# BEP33_2panel_test.net
KiCad netlist of a schematic drawn in EAGLE
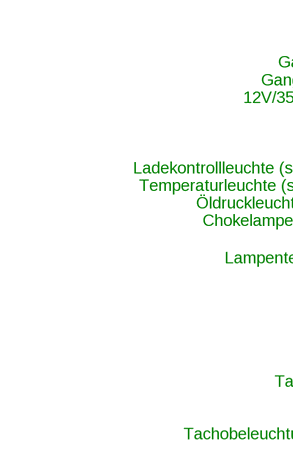
[diagram p0: schematic, sheet 1, part 1 of 2]
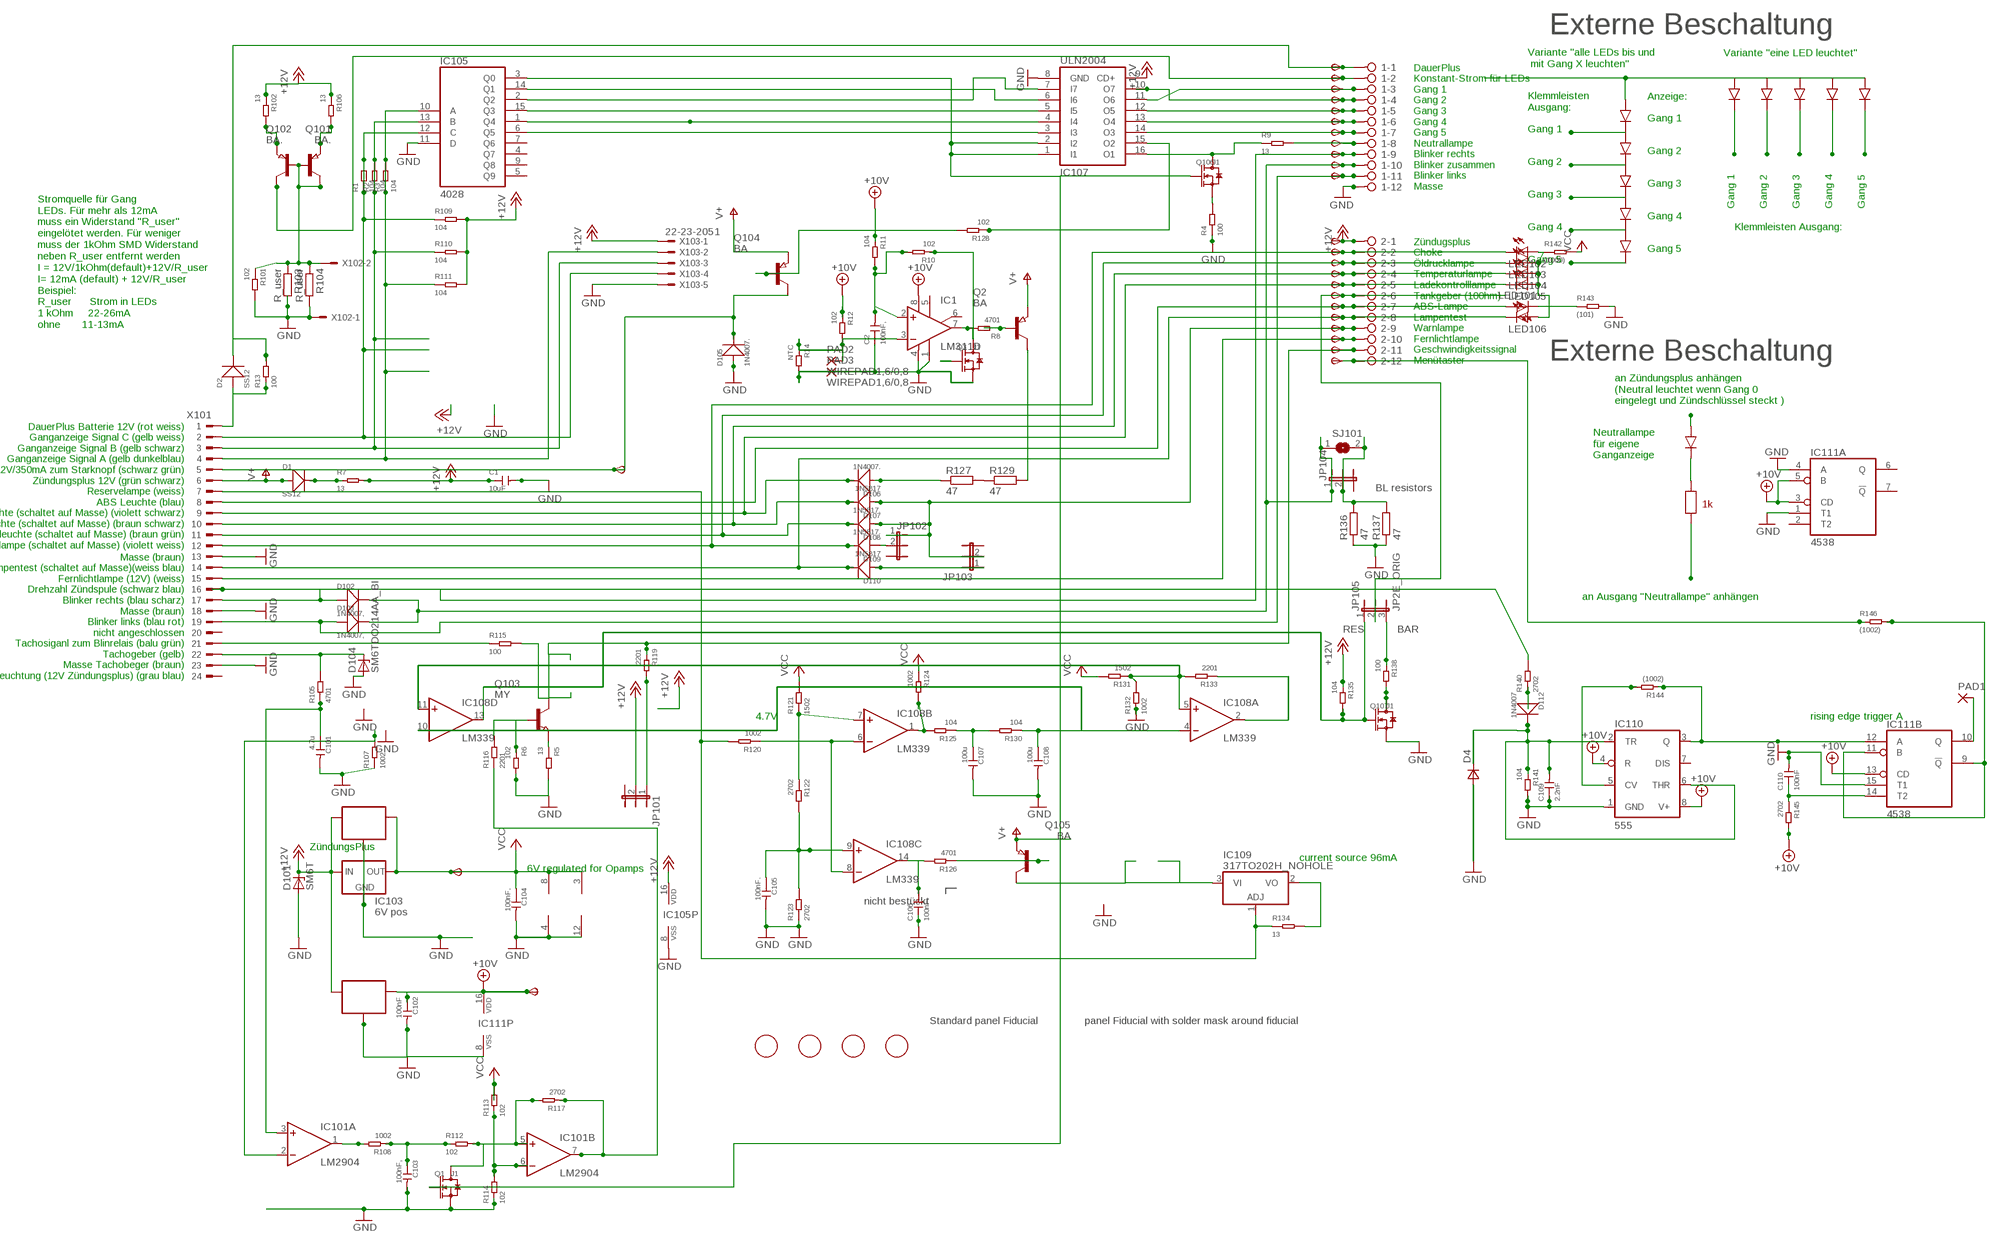
[diagram p1: schematic, sheet 1, part 2 of 2]
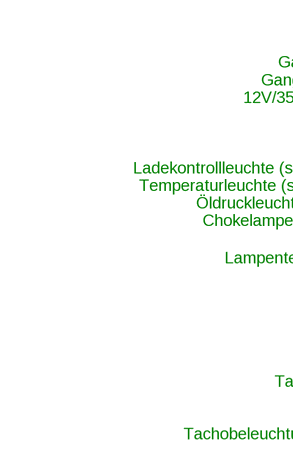
[diagram p2: schematic, sheet 2, part 1 of 2]
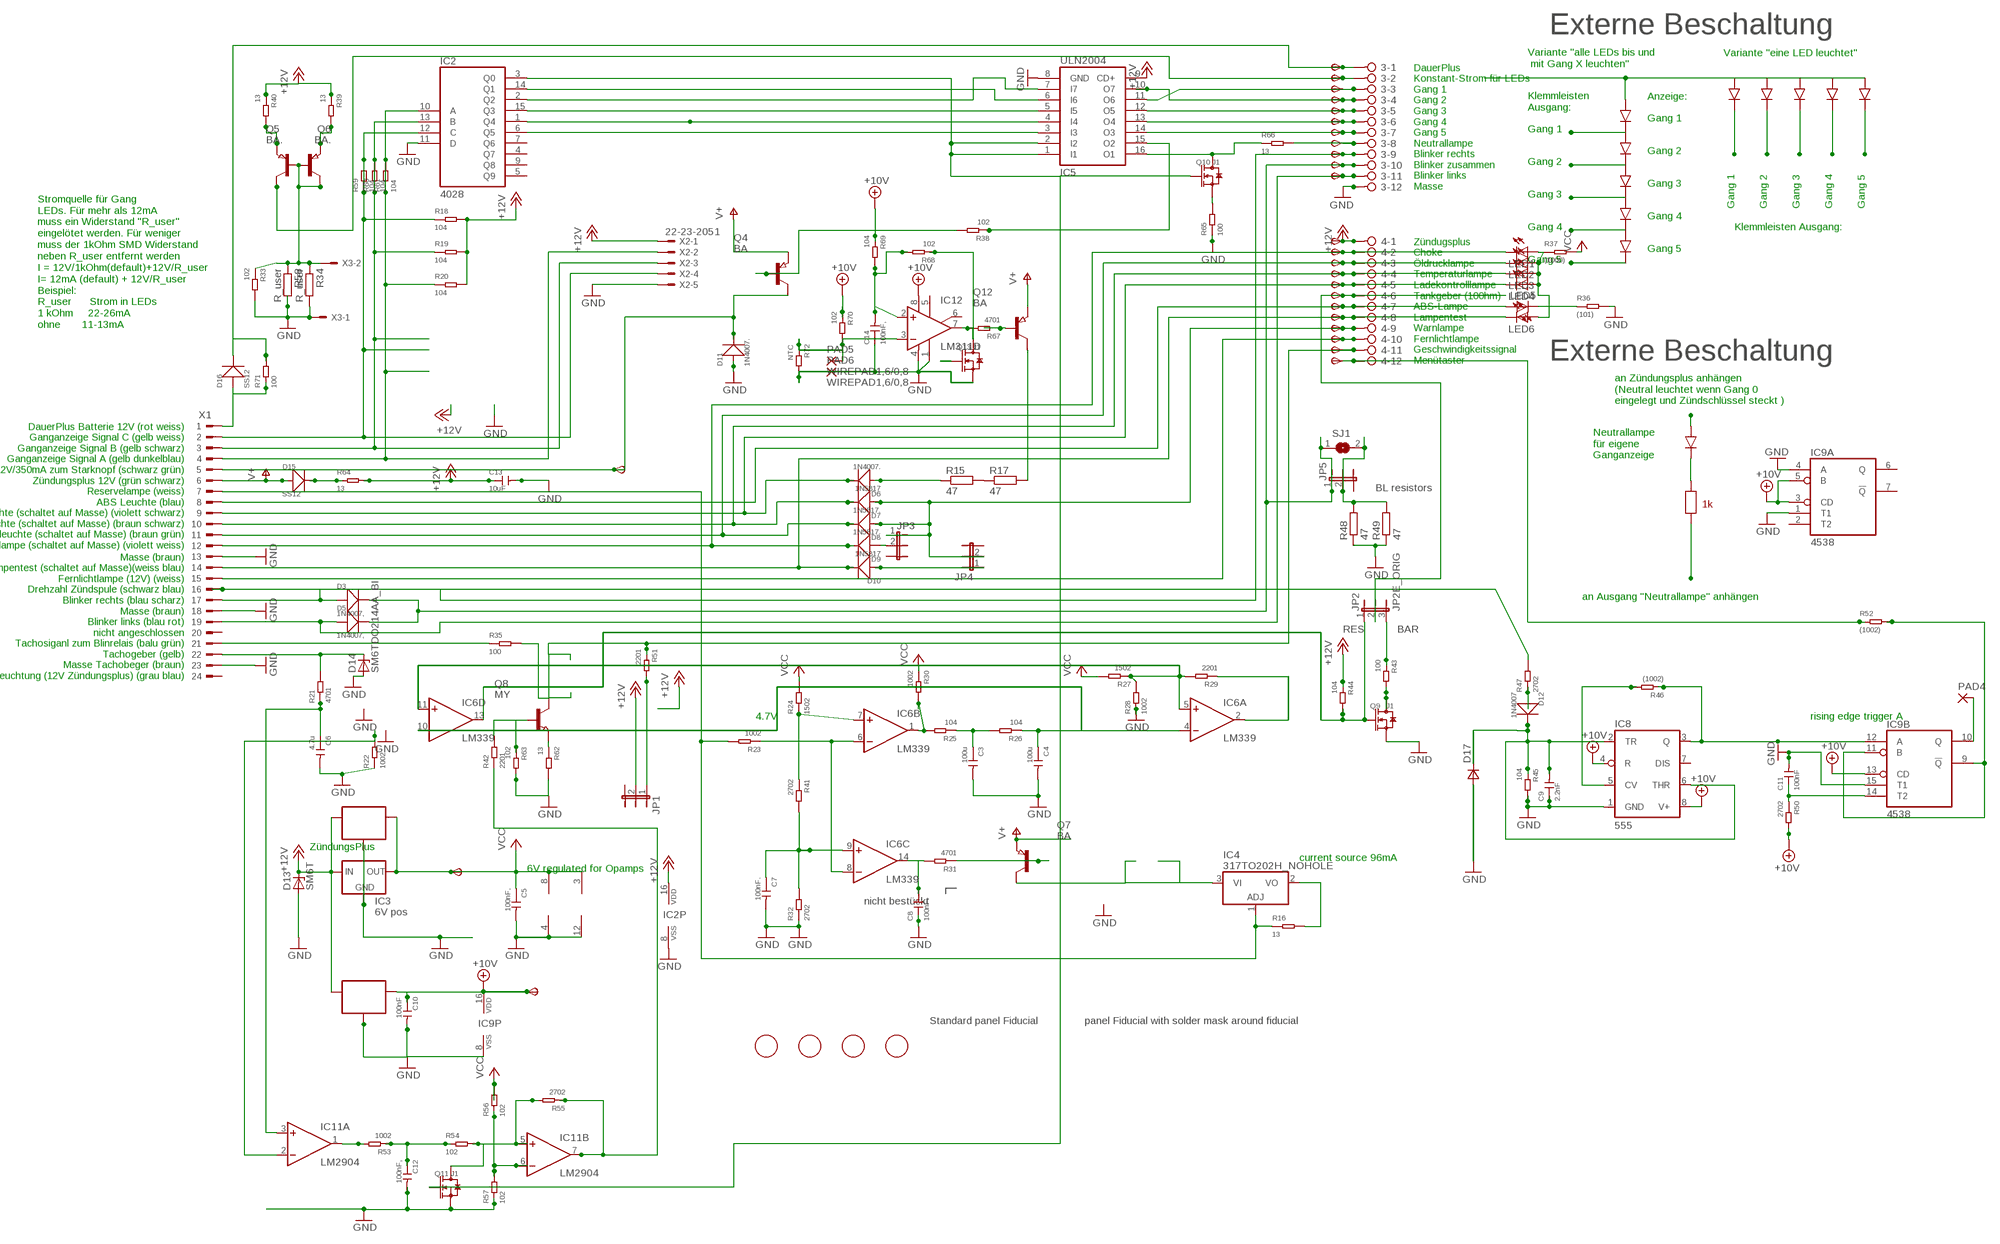
[diagram p3: schematic, sheet 2, part 2 of 2]

(export (version "E")
  (design (tool "Eeschema 10.0.6"))
  (components
    (comp (ref "3")
      (value "2081-1132")
      (footprint "eagle-import:12-PIN")
      (libsource (lib "eagle-import") (part "2081-1132"))
    )
    (comp (ref "4")
      (value "2081-1132")
      (footprint "eagle-import:12-PIN")
      (libsource (lib "eagle-import") (part "2081-1132"))
    )
    (comp (ref "6V1")
      (value "TPSB2.0")
      (footprint "eagle-import:B2.0")
      (libsource (lib "eagle-import") (part "TPSB2.0"))
    )
    (comp (ref "10V1")
      (value "TPSB2.0")
      (footprint "eagle-import:B2.0")
      (libsource (lib "eagle-import") (part "TPSB2.0"))
    )
    (comp (ref "C3")
      (value "100u")
      (footprint "eagle-import:C1206")
      (fields (field (name "MPN") "GRM31CR60J107ME39L"))
      (libsource (lib "eagle-import") (part "CERAMIC-100UF-6.3V-20%-X5R(1206)"))
    )
    (comp (ref "C4")
      (value "100u")
      (footprint "eagle-import:C1206")
      (fields (field (name "MPN") "GRM31CR60J107ME39L"))
      (libsource (lib "eagle-import") (part "CERAMIC-100UF-6.3V-20%-X5R(1206)"))
    )
    (comp (ref "C5")
      (value "100nF,")
      (footprint "eagle-import:C0805")
      (fields (field (name "MPN") "CC0805KRX7R9BB104"))
      (libsource (lib "eagle-import") (part "CERAMIC-100NF-50V-10%-X7R(0805)"))
    )
    (comp (ref "C6")
      (value "4.7u")
      (footprint "eagle-import:C0805")
      (fields (field (name "MPN") "CC0805KKX5R8BB475"))
      (libsource (lib "eagle-import") (part "CERAMIC-4.7UF-25V-10%-X5R(0805)"))
    )
    (comp (ref "C7")
      (value "100nF.")
      (footprint "eagle-import:C0805")
      (fields (field (name "MPN") "CC0805KRX7R9BB104"))
      (libsource (lib "eagle-import") (part "CERAMIC-100NF-50V-10%-X7R(0805)"))
    )
    (comp (ref "C8")
      (value "100nF.")
      (footprint "eagle-import:C0805")
      (fields (field (name "MPN") "CC0805KRX7R9BB104"))
      (libsource (lib "eagle-import") (part "CERAMIC-100NF-50V-10%-X7R(0805)"))
    )
    (comp (ref "C9")
      (value "2.2nF")
      (footprint "eagle-import:C0805")
      (fields (field (name "MPN") "CC0805KRX7R9BB104"))
      (libsource (lib "eagle-import") (part "CERAMIC-100NF-50V-10%-X7R(0805)"))
    )
    (comp (ref "C10")
      (value "100nF")
      (footprint "eagle-import:C0805")
      (fields (field (name "MPN") "CC0805KRX7R9BB104"))
      (libsource (lib "eagle-import") (part "CERAMIC-100NF-50V-10%-X7R(0805)"))
    )
    (comp (ref "C11")
      (value "100nF")
      (footprint "eagle-import:C0805")
      (fields (field (name "MPN") "CC0805KRX7R9BB104"))
      (libsource (lib "eagle-import") (part "CERAMIC-100NF-50V-10%-X7R(0805)"))
    )
    (comp (ref "C12")
      (value "100nF,")
      (footprint "eagle-import:C0805")
      (fields (field (name "MPN") "CC0805KRX7R9BB104"))
      (libsource (lib "eagle-import") (part "CERAMIC-100NF-50V-10%-X7R(0805)"))
    )
    (comp (ref "C13")
      (value "10uF")
      (footprint "eagle-import:C0805")
      (fields (field (name "MPN") "CC0805KRX7R9BB104"))
      (libsource (lib "eagle-import") (part "CERAMIC-100NF-50V-10%-X7R(0805)"))
    )
    (comp (ref "C14")
      (value "100nF,")
      (footprint "eagle-import:C0805")
      (fields (field (name "MPN") "CC0805KRX7R9BB104"))
      (libsource (lib "eagle-import") (part "CERAMIC-100NF-50V-10%-X7R(0805)"))
    )
    (comp (ref "D3")
      (value "1N4007,")
      (footprint "eagle-import:DO-214AC")
      (fields (field (name "MPN") "1N4007"))
      (libsource (lib "eagle-import") (part "DIODE-GEN-PURPOSE-1KV-1A(DO-214AC)"))
    )
    (comp (ref "D5")
      (value "1N4007,")
      (footprint "eagle-import:DO-214AC")
      (fields (field (name "MPN") "1N4007"))
      (libsource (lib "eagle-import") (part "DIODE-GEN-PURPOSE-1KV-1A(DO-214AC)"))
    )
    (comp (ref "D6")
      (value "1N4007.")
      (footprint "eagle-import:DO-214AC")
      (fields (field (name "MPN") "1N4007"))
      (libsource (lib "eagle-import") (part "DIODE-GEN-PURPOSE-1KV-1A(DO-214AC)"))
    )
    (comp (ref "D7")
      (value "1N5817")
      (footprint "eagle-import:DO-214AC_SLIM")
      (libsource (lib "eagle-import") (part "DIODE-GEN-PURPOSE-1KV-1A(DO-214AC)DO-214AC/1206"))
    )
    (comp (ref "D8")
      (value "1N5817.")
      (footprint "eagle-import:DO-214AC_SLIM")
      (libsource (lib "eagle-import") (part "DIODE-GEN-PURPOSE-1KV-1A(DO-214AC)DO-214AC/1206"))
    )
    (comp (ref "D9")
      (value "1N5817.")
      (footprint "eagle-import:DO-214AC_SLIM")
      (libsource (lib "eagle-import") (part "DIODE-GEN-PURPOSE-1KV-1A(DO-214AC)DO-214AC/1206"))
    )
    (comp (ref "D10")
      (value "1N5817")
      (footprint "eagle-import:DO-214AC_SLIM")
      (libsource (lib "eagle-import") (part "DIODE-GEN-PURPOSE-1KV-1A(DO-214AC)DO-214AC/1206"))
    )
    (comp (ref "D11")
      (value "1N4007.")
      (footprint "eagle-import:DO-214AC")
      (fields (field (name "MPN") "1N4007"))
      (libsource (lib "eagle-import") (part "DIODE-GEN-PURPOSE-1KV-1A(DO-214AC)"))
    )
    (comp (ref "D12")
      (value "1N4007")
      (footprint "eagle-import:DO-214AC")
      (libsource (lib "eagle-import") (part "DIODE-GEN-PURPOSE-1KV-1A(DO-214AC)"))
    )
    (comp (ref "D13")
      (value "SM6T")
      (footprint "eagle-import:DO214AA")
      (libsource (lib "eagle-import") (part "SM6T"))
    )
    (comp (ref "D14")
      (value "SM6TDO214AA_BI")
      (footprint "eagle-import:DO214AA_BI")
      (libsource (lib "eagle-import") (part "SM6TDO214AA_BI"))
    )
    (comp (ref "D15")
      (value "SS12")
      (footprint "eagle-import:DO-214AC_SLIM")
      (libsource (lib "eagle-import") (part "DIODE-GEN-PURPOSE-1KV-1A(DO-214AC)DO-214AC/1206"))
    )
    (comp (ref "D16")
      (value "SS12")
      (footprint "eagle-import:DO-214AC_SLIM")
      (libsource (lib "eagle-import") (part "DIODE-GEN-PURPOSE-1KV-1A(DO-214AC)DO-214AC/1206"))
    )
    (comp (ref "D17")
      (value "DSOD323")
      (footprint "eagle-import:SOD323")
      (fields (field (name "MPN") "CDSOD323-T05C"))
      (libsource (lib "eagle-import") (part "DSOD323"))
    )
    (comp (ref "FID3")
      (value "FIDUCIAL")
      (footprint "eagle-import:FIDUCIAL_1MM")
      (libsource (lib "eagle-import") (part "FIDUCIAL"))
    )
    (comp (ref "FID4")
      (value "FIDUCIAL")
      (footprint "eagle-import:FIDUCIAL_1MM")
      (libsource (lib "eagle-import") (part "FIDUCIAL"))
    )
    (comp (ref "FID5")
      (value "FIDUCIAL")
      (footprint "eagle-import:FIDUCIAL_1MM")
      (libsource (lib "eagle-import") (part "FIDUCIAL"))
    )
    (comp (ref "FID6")
      (value "FIDUCIAL")
      (footprint "eagle-import:FIDUCIAL_1MM")
      (libsource (lib "eagle-import") (part "FIDUCIAL"))
    )
    (comp (ref "IC2")
      (value "4028")
      (footprint "eagle-import:SO16")
      (libsource (lib "eagle-import") (part "4028D"))
    )
    (comp (ref "IC3")
      (value "6V pos")
      (footprint "eagle-import:78LXX")
      (libsource (lib "eagle-import") (part "v-reg_78LXX"))
    )
    (comp (ref "IC4")
      (value "317TO202H_NOHOLE")
      (footprint "eagle-import:TO220H_NOHOLE")
      (libsource (lib "eagle-import") (part "317TO202H_NOHOLE"))
    )
    (comp (ref "IC5")
      (value "ULN2004")
      (footprint "eagle-import:SO16")
      (libsource (lib "eagle-import") (part "ULN2004AD"))
    )
    (comp (ref "IC6")
      (value "LM339")
      (footprint "eagle-import:SO14")
      (libsource (lib "eagle-import") (part "LM339D"))
    )
    (comp (ref "IC7")
      (value "78L06")
      (footprint "eagle-import:SOT89_ROUND")
      (libsource (lib "eagle-import") (part "78LXXSOT89_ROUND"))
    )
    (comp (ref "IC8")
      (value "555")
      (footprint "eagle-import:SO08")
      (libsource (lib "eagle-import") (part "555DNE"))
    )
    (comp (ref "IC9")
      (value "4538")
      (footprint "eagle-import:SO16")
      (libsource (lib "eagle-import") (part "4538D"))
    )
    (comp (ref "IC10")
      (value "78L10")
      (footprint "eagle-import:SOT89_ROUND")
      (libsource (lib "eagle-import") (part "78LXXSOT89_ROUND"))
    )
    (comp (ref "IC11")
      (value "LM2904")
      (footprint "eagle-import:SO08")
      (libsource (lib "eagle-import") (part "LM358D"))
    )
    (comp (ref "IC12")
      (value "LM311D")
      (footprint "eagle-import:SO08")
      (libsource (lib "eagle-import") (part "LM311D"))
    )
    (comp (ref "JP1")
      (value "JP2EJP2_SMALLPADS")
      (footprint "eagle-import:JP2_SMALLPADS")
      (libsource (lib "eagle-import") (part "JP2EJP2_SMALLPADS"))
    )
    (comp (ref "JP2")
      (value "JP2E_ORIG")
      (footprint "eagle-import:JP2_ORIG_SMALLPADS")
      (libsource (lib "eagle-import") (part "JP2E_ORIG"))
    )
    (comp (ref "JP3")
      (value "JP2EJP2_SMALLPADS")
      (footprint "eagle-import:JP2_SMALLPADS")
      (libsource (lib "eagle-import") (part "JP2EJP2_SMALLPADS"))
    )
    (comp (ref "JP4")
      (value "JP2EJP2_SMALLPADS")
      (footprint "eagle-import:JP2_SMALLPADS")
      (libsource (lib "eagle-import") (part "JP2EJP2_SMALLPADS"))
    )
    (comp (ref "JP5")
      (value "JP2EJP2_SMALLPADS")
      (footprint "eagle-import:JP2_SMALLPADS")
      (libsource (lib "eagle-import") (part "JP2EJP2_SMALLPADS"))
    )
    (comp (ref "LED1")
      (value "LEDLD260")
      (footprint "eagle-import:LD260")
      (libsource (lib "eagle-import") (part "LEDLD260"))
    )
    (comp (ref "LED2")
      (value "LEDLD260")
      (footprint "eagle-import:LD260")
      (libsource (lib "eagle-import") (part "LEDLD260"))
    )
    (comp (ref "LED3")
      (value "LEDLD260")
      (footprint "eagle-import:LD260")
      (libsource (lib "eagle-import") (part "LEDLD260"))
    )
    (comp (ref "LED4")
      (value "LEDLD260")
      (footprint "eagle-import:LD260")
      (libsource (lib "eagle-import") (part "LEDLD260"))
    )
    (comp (ref "LED5")
      (value "LEDLD260")
      (footprint "eagle-import:LD260")
      (libsource (lib "eagle-import") (part "LEDLD260"))
    )
    (comp (ref "LED6")
      (value "LEDLD260")
      (footprint "eagle-import:LD260")
      (libsource (lib "eagle-import") (part "LEDLD260"))
    )
    (comp (ref "PAD4")
      (value "1,6/0,8")
      (footprint "eagle-import:1,6_0,8")
      (libsource (lib "eagle-import") (part "1,6/0,8"))
    )
    (comp (ref "PAD5")
      (value "WIREPAD1,6/0,8")
      (footprint "eagle-import:1,6_0,8")
      (libsource (lib "eagle-import") (part "WIREPAD1,6/0,8"))
    )
    (comp (ref "PAD6")
      (value "WIREPAD1,6/0,8")
      (footprint "eagle-import:1,6_0,8")
      (libsource (lib "eagle-import") (part "WIREPAD1,6/0,8"))
    )
    (comp (ref "Q4")
      (value "BA")
      (footprint "eagle-import:SOT89")
      (libsource (lib "eagle-import") (part "PNP-TRANSISTOR_SOT89"))
    )
    (comp (ref "Q5")
      (value "BA.")
      (footprint "eagle-import:SOT89")
      (libsource (lib "eagle-import") (part "PNP-TRANSISTOR_SOT89"))
    )
    (comp (ref "Q6")
      (value "BA.")
      (footprint "eagle-import:SOT89")
      (libsource (lib "eagle-import") (part "PNP-TRANSISTOR_SOT89"))
    )
    (comp (ref "Q7")
      (value "BA")
      (footprint "eagle-import:SOT89")
      (libsource (lib "eagle-import") (part "PNP-TRANSISTOR_SOT89"))
    )
    (comp (ref "Q8")
      (value "MY")
      (footprint "eagle-import:SOT89")
      (libsource (lib "eagle-import") (part "NPN-TRANSISTOR_SOT89"))
    )
    (comp (ref "Q9")
      (value "J1")
      (footprint "eagle-import:SOT-23")
      (fields (field (name "MPN") "BSS138W-7-F"))
      (libsource (lib "eagle-import") (part "SMD-MOSFET-N-CH-50V-200MA-BSS138W-7-F(SOT-23)"))
    )
    (comp (ref "Q10")
      (value "J1")
      (footprint "eagle-import:SOT-23")
      (fields (field (name "MPN") "BSS138W-7-F"))
      (libsource (lib "eagle-import") (part "SMD-MOSFET-N-CH-50V-200MA-BSS138W-7-F(SOT-23)"))
    )
    (comp (ref "Q11")
      (value "J1")
      (footprint "eagle-import:SOT-23")
      (fields (field (name "MPN") "BSS138W-7-F"))
      (libsource (lib "eagle-import") (part "SMD-MOSFET-N-CH-50V-200MA-BSS138W-7-F(SOT-23)"))
    )
    (comp (ref "Q12")
      (value "BA")
      (footprint "eagle-import:SOT89")
      (libsource (lib "eagle-import") (part "PNP-TRANSISTOR_SOT89"))
    )
    (comp (ref "Q13")
      (value "J1")
      (footprint "eagle-import:SOT-23")
      (fields (field (name "MPN") "BSS138W-7-F"))
      (libsource (lib "eagle-import") (part "SMD-MOSFET-N-CH-50V-200MA-BSS138W-7-F(SOT-23)"))
    )
    (comp (ref "R15")
      (value "47")
      (footprint "eagle-import:V235_17_1MM")
      (libsource (lib "eagle-import") (part "R-EU_V235/17_1MM"))
    )
    (comp (ref "R16")
      (value "13")
      (footprint "eagle-import:R1206")
      (fields (field (name "MPN") "RC1206JR-0713RL"))
      (libsource (lib "eagle-import") (part "SMD-RES-13R-5%-1/4W(1206)"))
    )
    (comp (ref "R17")
      (value "47")
      (footprint "eagle-import:V235_17_1MM")
      (libsource (lib "eagle-import") (part "R-EU_V235/17_1MM"))
    )
    (comp (ref "R18")
      (value "104")
      (footprint "eagle-import:R0805")
      (fields (field (name "MPN") "RC0805FR-0710KL"))
      (libsource (lib "eagle-import") (part "SMD-RES-10K-1%-1/8W(0805)"))
    )
    (comp (ref "R19")
      (value "104")
      (footprint "eagle-import:R0805")
      (fields (field (name "MPN") "RC0805FR-0710KL"))
      (libsource (lib "eagle-import") (part "SMD-RES-10K-1%-1/8W(0805)"))
    )
    (comp (ref "R20")
      (value "104")
      (footprint "eagle-import:R0805")
      (fields (field (name "MPN") "RC0805FR-0710KL"))
      (libsource (lib "eagle-import") (part "SMD-RES-10K-1%-1/8W(0805)"))
    )
    (comp (ref "R21")
      (value "4701")
      (footprint "eagle-import:R0805")
      (fields (field (name "MPN") "RC0805JR-074K7L"))
      (libsource (lib "eagle-import") (part "SMD-RES-4.7K-5%-1/8W(0805)"))
    )
    (comp (ref "R22")
      (value "1002")
      (footprint "eagle-import:R0805")
      (fields (field (name "MPN") "RC0805FR-0710KL"))
      (libsource (lib "eagle-import") (part "SMD-RES-10K-1%-1/8W(0805)"))
    )
    (comp (ref "R23")
      (value "1002")
      (footprint "eagle-import:R0805")
      (fields (field (name "MPN") "RC0805FR-0710KL"))
      (libsource (lib "eagle-import") (part "SMD-RES-10K-1%-1/8W(0805)"))
    )
    (comp (ref "R24")
      (value "1502")
      (footprint "eagle-import:R0805")
      (fields (field (name "MPN") "RC0805FR-0710KL"))
      (libsource (lib "eagle-import") (part "SMD-RES-10K-1%-1/8W(0805)"))
    )
    (comp (ref "R25")
      (value "104")
      (footprint "eagle-import:R0805")
      (fields (field (name "MPN") "RC0805FR-0710KL"))
      (libsource (lib "eagle-import") (part "SMD-RES-10K-1%-1/8W(0805)"))
    )
    (comp (ref "R26")
      (value "104")
      (footprint "eagle-import:R0805")
      (fields (field (name "MPN") "RC0805FR-0710KL"))
      (libsource (lib "eagle-import") (part "SMD-RES-10K-1%-1/8W(0805)"))
    )
    (comp (ref "R27")
      (value "1502")
      (footprint "eagle-import:R0805")
      (fields (field (name "MPN") "RC0805FR-0710KL"))
      (libsource (lib "eagle-import") (part "SMD-RES-10K-1%-1/8W(0805)"))
    )
    (comp (ref "R28")
      (value "1002")
      (footprint "eagle-import:R0805")
      (fields (field (name "MPN") "RC0805FR-0710KL"))
      (libsource (lib "eagle-import") (part "SMD-RES-10K-1%-1/8W(0805)"))
    )
    (comp (ref "R29")
      (value "2201")
      (footprint "eagle-import:R0805")
      (fields (field (name "MPN") "RC0805JR-072K2L"))
      (libsource (lib "eagle-import") (part "SMD-RES-2.2K-5%-1/8W(0805)"))
    )
    (comp (ref "R30")
      (value "1002")
      (footprint "eagle-import:R0805")
      (fields (field (name "MPN") "RC0805FR-0710KL"))
      (libsource (lib "eagle-import") (part "SMD-RES-10K-1%-1/8W(0805)"))
    )
    (comp (ref "R31")
      (value "4701")
      (footprint "eagle-import:R0805")
      (fields (field (name "MPN") "RC0805JR-074K7L"))
      (libsource (lib "eagle-import") (part "SMD-RES-4.7K-5%-1/8W(0805)"))
    )
    (comp (ref "R32")
      (value "2702")
      (footprint "eagle-import:R0805")
      (fields (field (name "MPN") "RC0805JR-074K7L"))
      (libsource (lib "eagle-import") (part "SMD-RES-4.7K-5%-1/8W(0805)"))
    )
    (comp (ref "R33")
      (value "102")
      (footprint "eagle-import:R0805")
      (fields (field (name "MPN") "RC0805JR-071KL"))
      (libsource (lib "eagle-import") (part "SMD-RES-1K-5%-1/8W(0805)"))
    )
    (comp (ref "R34")
      (value "R_user")
      (footprint "eagle-import:R0805")
      (libsource (lib "eagle-import") (part "R-EU_R0805"))
    )
    (comp (ref "R35")
      (value "100")
      (footprint "eagle-import:R0805")
      (fields (field (name "MPN") "RC0805JR-07220RL"))
      (libsource (lib "eagle-import") (part "SMD-RES-220R-5%-1/8W(0805)"))
    )
    (comp (ref "R36")
      (value "(101)")
      (footprint "eagle-import:R0805")
      (fields (field (name "MPN") "RC0805JR-07100RL"))
      (libsource (lib "eagle-import") (part "SMD-RES-100R-5%-1/8W(0805)"))
    )
    (comp (ref "R37")
      (value "(1000)")
      (footprint "eagle-import:R0805")
      (fields (field (name "MPN") "RC0805JR-07100RL"))
      (libsource (lib "eagle-import") (part "SMD-RES-100R-5%-1/8W(0805)"))
    )
    (comp (ref "R38")
      (value "102")
      (footprint "eagle-import:R0805")
      (fields (field (name "MPN") "RC0805JR-071KL"))
      (libsource (lib "eagle-import") (part "SMD-RES-1K-5%-1/8W(0805)"))
    )
    (comp (ref "R39")
      (value "13")
      (footprint "eagle-import:R1206")
      (fields (field (name "MPN") "RC1206JR-0713RL"))
      (libsource (lib "eagle-import") (part "SMD-RES-13R-5%-1/4W(1206)"))
    )
    (comp (ref "R40")
      (value "13")
      (footprint "eagle-import:R1206")
      (fields (field (name "MPN") "RC1206JR-0713RL"))
      (libsource (lib "eagle-import") (part "SMD-RES-13R-5%-1/4W(1206)"))
    )
    (comp (ref "R41")
      (value "2702")
      (footprint "eagle-import:R0805")
      (fields (field (name "MPN") "RC0805JR-074K7L"))
      (libsource (lib "eagle-import") (part "SMD-RES-4.7K-5%-1/8W(0805)"))
    )
    (comp (ref "R42")
      (value "2201")
      (footprint "eagle-import:R0805")
      (fields (field (name "MPN") "RC0805JR-074K7L"))
      (libsource (lib "eagle-import") (part "SMD-RES-4.7K-5%-1/8W(0805)"))
    )
    (comp (ref "R43")
      (value "100")
      (footprint "eagle-import:R0805")
      (fields (field (name "MPN") "RC0805JR-072K2L"))
      (libsource (lib "eagle-import") (part "SMD-RES-2.2K-5%-1/8W(0805)"))
    )
    (comp (ref "R44")
      (value "104")
      (footprint "eagle-import:R0805")
      (fields (field (name "MPN") "RC0805FR-0710KL"))
      (libsource (lib "eagle-import") (part "SMD-RES-10K-1%-1/8W(0805)"))
    )
    (comp (ref "R45")
      (value "104")
      (footprint "eagle-import:R0805")
      (fields (field (name "MPN") "RC0805FR-0710KL"))
      (libsource (lib "eagle-import") (part "SMD-RES-10K-1%-1/8W(0805)"))
    )
    (comp (ref "R46")
      (value "(1002)")
      (footprint "eagle-import:R0805")
      (fields (field (name "MPN") "RC0805FR-0710KL"))
      (libsource (lib "eagle-import") (part "SMD-RES-10K-1%-1/8W(0805)"))
    )
    (comp (ref "R47")
      (value "2702")
      (footprint "eagle-import:R0805")
      (fields (field (name "MPN") "RC0805FR-0710KL"))
      (libsource (lib "eagle-import") (part "SMD-RES-10K-1%-1/8W(0805)"))
    )
    (comp (ref "R48")
      (value "47")
      (footprint "eagle-import:V235_17_1MM")
      (libsource (lib "eagle-import") (part "R-EU_V235/17_1MM"))
    )
    (comp (ref "R49")
      (value "47")
      (footprint "eagle-import:V235_17_1MM")
      (libsource (lib "eagle-import") (part "R-EU_V235/17_1MM"))
    )
    (comp (ref "R50")
      (value "2702")
      (footprint "eagle-import:R0805")
      (fields (field (name "MPN") "RC0805JR-074K7L"))
      (libsource (lib "eagle-import") (part "SMD-RES-4.7K-5%-1/8W(0805)"))
    )
    (comp (ref "R51")
      (value "2201")
      (footprint "eagle-import:R0805")
      (fields (field (name "MPN") "RC0805JR-072K2L"))
      (libsource (lib "eagle-import") (part "SMD-RES-2.2K-5%-1/8W(0805)"))
    )
    (comp (ref "R52")
      (value "(1002)")
      (footprint "eagle-import:R0805")
      (fields (field (name "MPN") "RC0805JR-074K7L"))
      (libsource (lib "eagle-import") (part "SMD-RES-4.7K-5%-1/8W(0805)"))
    )
    (comp (ref "R53")
      (value "1002")
      (footprint "eagle-import:R0805")
      (fields (field (name "MPN") "RC0805FR-0710KL"))
      (libsource (lib "eagle-import") (part "SMD-RES-10K-1%-1/8W(0805)"))
    )
    (comp (ref "R54")
      (value "102")
      (footprint "eagle-import:R0805")
      (fields (field (name "MPN") "RC0805JR-071KL"))
      (libsource (lib "eagle-import") (part "SMD-RES-1K-5%-1/8W(0805)"))
    )
    (comp (ref "R55")
      (value "2702")
      (footprint "eagle-import:R0805")
      (fields (field (name "MPN") "RC0805JR-074K7L"))
      (libsource (lib "eagle-import") (part "SMD-RES-4.7K-5%-1/8W(0805)"))
    )
    (comp (ref "R56")
      (value "102")
      (footprint "eagle-import:R0805")
      (fields (field (name "MPN") "RC0805JR-071KL"))
      (libsource (lib "eagle-import") (part "SMD-RES-1K-5%-1/8W(0805)"))
    )
    (comp (ref "R57")
      (value "102")
      (footprint "eagle-import:R0805")
      (fields (field (name "MPN") "RC0805JR-071KL"))
      (libsource (lib "eagle-import") (part "SMD-RES-1K-5%-1/8W(0805)"))
    )
    (comp (ref "R58")
      (value "R_user")
      (footprint "eagle-import:R0805")
      (libsource (lib "eagle-import") (part "R-EU_R0805"))
    )
    (comp (ref "R59")
      (value "104")
      (footprint "eagle-import:R0805")
      (fields (field (name "MPN") "RC0805FR-0710KL"))
      (libsource (lib "eagle-import") (part "SMD-RES-10K-1%-1/8W(0805)"))
    )
    (comp (ref "R60")
      (value "104")
      (footprint "eagle-import:R0805")
      (fields (field (name "MPN") "RC0805FR-0710KL"))
      (libsource (lib "eagle-import") (part "SMD-RES-10K-1%-1/8W(0805)"))
    )
    (comp (ref "R61")
      (value "104")
      (footprint "eagle-import:R0805")
      (fields (field (name "MPN") "RC0805FR-0710KL"))
      (libsource (lib "eagle-import") (part "SMD-RES-10K-1%-1/8W(0805)"))
    )
    (comp (ref "R62")
      (value "13")
      (footprint "eagle-import:R1206")
      (fields (field (name "MPN") "RC1206JR-0713RL"))
      (libsource (lib "eagle-import") (part "SMD-RES-13R-5%-1/4W(1206)"))
    )
    (comp (ref "R63")
      (value "102")
      (footprint "eagle-import:R0805")
      (fields (field (name "MPN") "RC0805JR-071KL"))
      (libsource (lib "eagle-import") (part "SMD-RES-1K-5%-1/8W(0805)"))
    )
    (comp (ref "R64")
      (value "13")
      (footprint "eagle-import:R1206")
      (fields (field (name "MPN") "RC1206JR-0713RL"))
      (libsource (lib "eagle-import") (part "SMD-RES-13R-5%-1/4W(1206)"))
    )
    (comp (ref "R65")
      (value "100")
      (footprint "eagle-import:R0805")
      (fields (field (name "MPN") "RC0805JR-07220RL"))
      (libsource (lib "eagle-import") (part "SMD-RES-220R-5%-1/8W(0805)"))
    )
    (comp (ref "R66")
      (value "13")
      (footprint "eagle-import:R1206")
      (fields (field (name "MPN") "RC1206JR-0713RL"))
      (libsource (lib "eagle-import") (part "SMD-RES-13R-5%-1/4W(1206)"))
    )
    (comp (ref "R67")
      (value "4701")
      (footprint "eagle-import:R0805")
      (fields (field (name "MPN") "RC0805JR-074K7L"))
      (libsource (lib "eagle-import") (part "SMD-RES-4.7K-5%-1/8W(0805)"))
    )
    (comp (ref "R68")
      (value "102")
      (footprint "eagle-import:R0805")
      (fields (field (name "MPN") "RC0805JR-071KL"))
      (libsource (lib "eagle-import") (part "SMD-RES-1K-5%-1/8W(0805)"))
    )
    (comp (ref "R69")
      (value "104")
      (footprint "eagle-import:R0805")
      (fields (field (name "MPN") "RC0805FR-0710KL"))
      (libsource (lib "eagle-import") (part "SMD-RES-10K-1%-1/8W(0805)"))
    )
    (comp (ref "R70")
      (value "102")
      (footprint "eagle-import:R0805")
      (fields (field (name "MPN") "RC0805JR-071KL"))
      (libsource (lib "eagle-import") (part "SMD-RES-1K-5%-1/8W(0805)"))
    )
    (comp (ref "R71")
      (value "100")
      (footprint "eagle-import:R0805")
      (fields (field (name "MPN") "RC0805JR-07220RL"))
      (libsource (lib "eagle-import") (part "SMD-RES-220R-5%-1/8W(0805)"))
    )
    (comp (ref "R72")
      (value "NTC")
      (footprint "eagle-import:R0805")
      (fields (field (name "MPN") "RC0805JR-071KL"))
      (libsource (lib "eagle-import") (part "SMD-RES-1K-5%-1/8W(0805)"))
    )
    (comp (ref "SJ1") (value "SJ") (footprint "eagle-import:SJ") (libsource (lib "eagle-import") (part "SJ")))
    (comp (ref "START1")
      (value "TPSB2.0")
      (footprint "eagle-import:B2.0")
      (libsource (lib "eagle-import") (part "TPSB2.0"))
    )
    (comp (ref "TP14")
      (value "TPSB2.0")
      (footprint "eagle-import:B2.0")
      (libsource (lib "eagle-import") (part "TPSB2.0"))
    )
    (comp (ref "TP15")
      (value "TPSB2.0")
      (footprint "eagle-import:B2.0")
      (libsource (lib "eagle-import") (part "TPSB2.0"))
    )
    (comp (ref "TP20")
      (value "TPSB2.0")
      (footprint "eagle-import:B2.0")
      (libsource (lib "eagle-import") (part "TPSB2.0"))
    )
    (comp (ref "TP27")
      (value "TPSB2.0")
      (footprint "eagle-import:B2.0")
      (libsource (lib "eagle-import") (part "TPSB2.0"))
    )
    (comp (ref "TP28")
      (value "TPSB2.0")
      (footprint "eagle-import:B2.0")
      (libsource (lib "eagle-import") (part "TPSB2.0"))
    )
    (comp (ref "TP29")
      (value "TPSB2.0")
      (footprint "eagle-import:B2.0")
      (libsource (lib "eagle-import") (part "TPSB2.0"))
    )
    (comp (ref "TP30")
      (value "TPSB2.0")
      (footprint "eagle-import:B2.0")
      (libsource (lib "eagle-import") (part "TPSB2.0"))
    )
    (comp (ref "TP31")
      (value "TPSB2.0")
      (footprint "eagle-import:B2.0")
      (libsource (lib "eagle-import") (part "TPSB2.0"))
    )
    (comp (ref "TP32")
      (value "TPSB2.0")
      (footprint "eagle-import:B2.0")
      (libsource (lib "eagle-import") (part "TPSB2.0"))
    )
    (comp (ref "TP33")
      (value "TPSB2.0")
      (footprint "eagle-import:B2.0")
      (libsource (lib "eagle-import") (part "TPSB2.0"))
    )
    (comp (ref "TP34")
      (value "TPSB2.0")
      (footprint "eagle-import:B2.0")
      (libsource (lib "eagle-import") (part "TPSB2.0"))
    )
    (comp (ref "TP35")
      (value "TPSB2.0")
      (footprint "eagle-import:B2.0")
      (libsource (lib "eagle-import") (part "TPSB2.0"))
    )
    (comp (ref "TP36")
      (value "TPSB2.0")
      (footprint "eagle-import:B2.0")
      (libsource (lib "eagle-import") (part "TPSB2.0"))
    )
    (comp (ref "TP37")
      (value "TPSB2.0")
      (footprint "eagle-import:B2.0")
      (libsource (lib "eagle-import") (part "TPSB2.0"))
    )
    (comp (ref "TP38")
      (value "TPSB2.0")
      (footprint "eagle-import:B2.0")
      (libsource (lib "eagle-import") (part "TPSB2.0"))
    )
    (comp (ref "TP39")
      (value "TPSB2.0")
      (footprint "eagle-import:B2.0")
      (libsource (lib "eagle-import") (part "TPSB2.0"))
    )
    (comp (ref "TP40")
      (value "TPSB2.0")
      (footprint "eagle-import:B2.0")
      (libsource (lib "eagle-import") (part "TPSB2.0"))
    )
    (comp (ref "TP41")
      (value "TPSB2.0")
      (footprint "eagle-import:B2.0")
      (libsource (lib "eagle-import") (part "TPSB2.0"))
    )
    (comp (ref "TP42")
      (value "TPSB1,27")
      (footprint "eagle-import:B1,27")
      (libsource (lib "eagle-import") (part "TPSB1,27"))
    )
    (comp (ref "TP43")
      (value "TPSB2.0")
      (footprint "eagle-import:B2.0")
      (libsource (lib "eagle-import") (part "TPSB2.0"))
    )
    (comp (ref "TP44")
      (value "TPSB2.0")
      (footprint "eagle-import:B2.0")
      (libsource (lib "eagle-import") (part "TPSB2.0"))
    )
    (comp (ref "TP45")
      (value "TPSB2.0")
      (footprint "eagle-import:B2.0")
      (libsource (lib "eagle-import") (part "TPSB2.0"))
    )
    (comp (ref "TP46")
      (value "TPSB2.0")
      (footprint "eagle-import:B2.0")
      (libsource (lib "eagle-import") (part "TPSB2.0"))
    )
    (comp (ref "X1")
      (value "CON_BMWV2")
      (footprint "eagle-import:24-PIN_V2")
      (libsource (lib "eagle-import") (part "CON_BMWV2"))
    )
    (comp (ref "X2")
      (value "22-23-2051")
      (footprint "eagle-import:22-23-2051")
      (fields (field (name "MF") "MOLEX"))
      (libsource (lib "eagle-import") (part "22-23-2051"))
    )
    (comp (ref "X3")
      (value "22-23-2021")
      (footprint "eagle-import:22-23-2021")
      (fields (field (name "MF") "MOLEX"))
      (libsource (lib "eagle-import") (part "22-23-2021"))
    )
    (comp (ref "1")
      (value "2081-1132")
      (footprint "eagle-import:12-PIN")
      (libsource (lib "eagle-import") (part "2081-1132"))
    )
    (comp (ref "2")
      (value "2081-1132")
      (footprint "eagle-import:12-PIN")
      (libsource (lib "eagle-import") (part "2081-1132"))
    )
    (comp (ref "6V")
      (value "TPSB2.0")
      (footprint "eagle-import:B2.0")
      (libsource (lib "eagle-import") (part "TPSB2.0"))
    )
    (comp (ref "10V")
      (value "TPSB2.0")
      (footprint "eagle-import:B2.0")
      (libsource (lib "eagle-import") (part "TPSB2.0"))
    )
    (comp (ref "C1")
      (value "10uF")
      (footprint "eagle-import:C0805")
      (fields (field (name "MPN") "CC0805KRX7R9BB104"))
      (libsource (lib "eagle-import") (part "CERAMIC-100NF-50V-10%-X7R(0805)"))
    )
    (comp (ref "C2")
      (value "100nF,")
      (footprint "eagle-import:C0805")
      (fields (field (name "MPN") "CC0805KRX7R9BB104"))
      (libsource (lib "eagle-import") (part "CERAMIC-100NF-50V-10%-X7R(0805)"))
    )
    (comp (ref "C101")
      (value "4.7u")
      (footprint "eagle-import:C0805")
      (fields (field (name "MPN") "CC0805KKX5R8BB475"))
      (libsource (lib "eagle-import") (part "CERAMIC-4.7UF-25V-10%-X5R(0805)"))
    )
    (comp (ref "C102")
      (value "100nF")
      (footprint "eagle-import:C0805")
      (fields (field (name "MPN") "CC0805KRX7R9BB104"))
      (libsource (lib "eagle-import") (part "CERAMIC-100NF-50V-10%-X7R(0805)"))
    )
    (comp (ref "C103")
      (value "100nF,")
      (footprint "eagle-import:C0805")
      (fields (field (name "MPN") "CC0805KRX7R9BB104"))
      (libsource (lib "eagle-import") (part "CERAMIC-100NF-50V-10%-X7R(0805)"))
    )
    (comp (ref "C104")
      (value "100nF,")
      (footprint "eagle-import:C0805")
      (fields (field (name "MPN") "CC0805KRX7R9BB104"))
      (libsource (lib "eagle-import") (part "CERAMIC-100NF-50V-10%-X7R(0805)"))
    )
    (comp (ref "C105")
      (value "100nF.")
      (footprint "eagle-import:C0805")
      (fields (field (name "MPN") "CC0805KRX7R9BB104"))
      (libsource (lib "eagle-import") (part "CERAMIC-100NF-50V-10%-X7R(0805)"))
    )
    (comp (ref "C106")
      (value "100nF.")
      (footprint "eagle-import:C0805")
      (fields (field (name "MPN") "CC0805KRX7R9BB104"))
      (libsource (lib "eagle-import") (part "CERAMIC-100NF-50V-10%-X7R(0805)"))
    )
    (comp (ref "C107")
      (value "100u")
      (footprint "eagle-import:C1206")
      (fields (field (name "MPN") "GRM31CR60J107ME39L"))
      (libsource (lib "eagle-import") (part "CERAMIC-100UF-6.3V-20%-X5R(1206)"))
    )
    (comp (ref "C108")
      (value "100u")
      (footprint "eagle-import:C1206")
      (fields (field (name "MPN") "GRM31CR60J107ME39L"))
      (libsource (lib "eagle-import") (part "CERAMIC-100UF-6.3V-20%-X5R(1206)"))
    )
    (comp (ref "C109")
      (value "2.2nF")
      (footprint "eagle-import:C0805")
      (fields (field (name "MPN") "CC0805KRX7R9BB104"))
      (libsource (lib "eagle-import") (part "CERAMIC-100NF-50V-10%-X7R(0805)"))
    )
    (comp (ref "C110")
      (value "100nF")
      (footprint "eagle-import:C0805")
      (fields (field (name "MPN") "CC0805KRX7R9BB104"))
      (libsource (lib "eagle-import") (part "CERAMIC-100NF-50V-10%-X7R(0805)"))
    )
    (comp (ref "D1")
      (value "SS12")
      (footprint "eagle-import:DO-214AC_SLIM")
      (libsource (lib "eagle-import") (part "DIODE-GEN-PURPOSE-1KV-1A(DO-214AC)DO-214AC/1206"))
    )
    (comp (ref "D2")
      (value "SS12")
      (footprint "eagle-import:DO-214AC_SLIM")
      (libsource (lib "eagle-import") (part "DIODE-GEN-PURPOSE-1KV-1A(DO-214AC)DO-214AC/1206"))
    )
    (comp (ref "D4")
      (value "DSOD323")
      (footprint "eagle-import:SOD323")
      (fields (field (name "MPN") "CDSOD323-T05C"))
      (libsource (lib "eagle-import") (part "DSOD323"))
    )
    (comp (ref "D101")
      (value "SM6T")
      (footprint "eagle-import:DO214AA")
      (libsource (lib "eagle-import") (part "SM6T"))
    )
    (comp (ref "D102")
      (value "1N4007,")
      (footprint "eagle-import:DO-214AC")
      (fields (field (name "MPN") "1N4007"))
      (libsource (lib "eagle-import") (part "DIODE-GEN-PURPOSE-1KV-1A(DO-214AC)"))
    )
    (comp (ref "D103")
      (value "1N4007,")
      (footprint "eagle-import:DO-214AC")
      (fields (field (name "MPN") "1N4007"))
      (libsource (lib "eagle-import") (part "DIODE-GEN-PURPOSE-1KV-1A(DO-214AC)"))
    )
    (comp (ref "D104")
      (value "SM6TDO214AA_BI")
      (footprint "eagle-import:DO214AA_BI")
      (libsource (lib "eagle-import") (part "SM6TDO214AA_BI"))
    )
    (comp (ref "D105")
      (value "1N4007.")
      (footprint "eagle-import:DO-214AC")
      (fields (field (name "MPN") "1N4007"))
      (libsource (lib "eagle-import") (part "DIODE-GEN-PURPOSE-1KV-1A(DO-214AC)"))
    )
    (comp (ref "D106")
      (value "1N4007.")
      (footprint "eagle-import:DO-214AC")
      (fields (field (name "MPN") "1N4007"))
      (libsource (lib "eagle-import") (part "DIODE-GEN-PURPOSE-1KV-1A(DO-214AC)"))
    )
    (comp (ref "D107")
      (value "1N5817")
      (footprint "eagle-import:DO-214AC_SLIM")
      (libsource (lib "eagle-import") (part "DIODE-GEN-PURPOSE-1KV-1A(DO-214AC)DO-214AC/1206"))
    )
    (comp (ref "D108")
      (value "1N5817.")
      (footprint "eagle-import:DO-214AC_SLIM")
      (libsource (lib "eagle-import") (part "DIODE-GEN-PURPOSE-1KV-1A(DO-214AC)DO-214AC/1206"))
    )
    (comp (ref "D109")
      (value "1N5817.")
      (footprint "eagle-import:DO-214AC_SLIM")
      (libsource (lib "eagle-import") (part "DIODE-GEN-PURPOSE-1KV-1A(DO-214AC)DO-214AC/1206"))
    )
    (comp (ref "D110")
      (value "1N5817")
      (footprint "eagle-import:DO-214AC_SLIM")
      (libsource (lib "eagle-import") (part "DIODE-GEN-PURPOSE-1KV-1A(DO-214AC)DO-214AC/1206"))
    )
    (comp (ref "D112")
      (value "1N4007")
      (footprint "eagle-import:DO-214AC")
      (libsource (lib "eagle-import") (part "DIODE-GEN-PURPOSE-1KV-1A(DO-214AC)"))
    )
    (comp (ref "FID101")
      (value "FIDUCIAL")
      (footprint "eagle-import:FIDUCIAL_1MM")
      (libsource (lib "eagle-import") (part "FIDUCIAL"))
    )
    (comp (ref "FID102")
      (value "FIDUCIAL")
      (footprint "eagle-import:FIDUCIAL_1MM")
      (libsource (lib "eagle-import") (part "FIDUCIAL"))
    )
    (comp (ref "FID103")
      (value "FIDUCIAL")
      (footprint "eagle-import:FIDUCIAL_1MM")
      (libsource (lib "eagle-import") (part "FIDUCIAL"))
    )
    (comp (ref "FID104")
      (value "FIDUCIAL")
      (footprint "eagle-import:FIDUCIAL_1MM")
      (libsource (lib "eagle-import") (part "FIDUCIAL"))
    )
    (comp (ref "IC1")
      (value "LM311D")
      (footprint "eagle-import:SO08")
      (libsource (lib "eagle-import") (part "LM311D"))
    )
    (comp (ref "IC101")
      (value "LM2904")
      (footprint "eagle-import:SO08")
      (libsource (lib "eagle-import") (part "LM358D"))
    )
    (comp (ref "IC102")
      (value "78L06")
      (footprint "eagle-import:SOT89_ROUND")
      (libsource (lib "eagle-import") (part "78LXXSOT89_ROUND"))
    )
    (comp (ref "IC103")
      (value "6V pos")
      (footprint "eagle-import:78LXX")
      (libsource (lib "eagle-import") (part "v-reg_78LXX"))
    )
    (comp (ref "IC104")
      (value "78L10")
      (footprint "eagle-import:SOT89_ROUND")
      (libsource (lib "eagle-import") (part "78LXXSOT89_ROUND"))
    )
    (comp (ref "IC105")
      (value "4028")
      (footprint "eagle-import:SO16")
      (libsource (lib "eagle-import") (part "4028D"))
    )
    (comp (ref "IC107")
      (value "ULN2004")
      (footprint "eagle-import:SO16")
      (libsource (lib "eagle-import") (part "ULN2004AD"))
    )
    (comp (ref "IC108")
      (value "LM339")
      (footprint "eagle-import:SO14")
      (libsource (lib "eagle-import") (part "LM339D"))
    )
    (comp (ref "IC109")
      (value "317TO202H_NOHOLE")
      (footprint "eagle-import:TO220H_NOHOLE")
      (libsource (lib "eagle-import") (part "317TO202H_NOHOLE"))
    )
    (comp (ref "IC110")
      (value "555")
      (footprint "eagle-import:SO08")
      (libsource (lib "eagle-import") (part "555DNE"))
    )
    (comp (ref "IC111")
      (value "4538")
      (footprint "eagle-import:SO16")
      (libsource (lib "eagle-import") (part "4538D"))
    )
    (comp (ref "JP101")
      (value "JP2EJP2_SMALLPADS")
      (footprint "eagle-import:JP2_SMALLPADS")
      (libsource (lib "eagle-import") (part "JP2EJP2_SMALLPADS"))
    )
    (comp (ref "JP102")
      (value "JP2EJP2_SMALLPADS")
      (footprint "eagle-import:JP2_SMALLPADS")
      (libsource (lib "eagle-import") (part "JP2EJP2_SMALLPADS"))
    )
    (comp (ref "JP103")
      (value "JP2EJP2_SMALLPADS")
      (footprint "eagle-import:JP2_SMALLPADS")
      (libsource (lib "eagle-import") (part "JP2EJP2_SMALLPADS"))
    )
    (comp (ref "JP104")
      (value "JP2EJP2_SMALLPADS")
      (footprint "eagle-import:JP2_SMALLPADS")
      (libsource (lib "eagle-import") (part "JP2EJP2_SMALLPADS"))
    )
    (comp (ref "JP105")
      (value "JP2E_ORIG")
      (footprint "eagle-import:JP2_ORIG_SMALLPADS")
      (libsource (lib "eagle-import") (part "JP2E_ORIG"))
    )
    (comp (ref "LED101")
      (value "LEDLD260")
      (footprint "eagle-import:LD260")
      (libsource (lib "eagle-import") (part "LEDLD260"))
    )
    (comp (ref "LED102")
      (value "LEDLD260")
      (footprint "eagle-import:LD260")
      (libsource (lib "eagle-import") (part "LEDLD260"))
    )
    (comp (ref "LED103")
      (value "LEDLD260")
      (footprint "eagle-import:LD260")
      (libsource (lib "eagle-import") (part "LEDLD260"))
    )
    (comp (ref "LED104")
      (value "LEDLD260")
      (footprint "eagle-import:LD260")
      (libsource (lib "eagle-import") (part "LEDLD260"))
    )
    (comp (ref "LED105")
      (value "LEDLD260")
      (footprint "eagle-import:LD260")
      (libsource (lib "eagle-import") (part "LEDLD260"))
    )
    (comp (ref "LED106")
      (value "LEDLD260")
      (footprint "eagle-import:LD260")
      (libsource (lib "eagle-import") (part "LEDLD260"))
    )
    (comp (ref "PAD1")
      (value "1,6/0,8")
      (footprint "eagle-import:1,6_0,8")
      (libsource (lib "eagle-import") (part "1,6/0,8"))
    )
    (comp (ref "PAD2")
      (value "WIREPAD1,6/0,8")
      (footprint "eagle-import:1,6_0,8")
      (libsource (lib "eagle-import") (part "WIREPAD1,6/0,8"))
    )
    (comp (ref "PAD3")
      (value "WIREPAD1,6/0,8")
      (footprint "eagle-import:1,6_0,8")
      (libsource (lib "eagle-import") (part "WIREPAD1,6/0,8"))
    )
    (comp (ref "Q1")
      (value "J1")
      (footprint "eagle-import:SOT-23")
      (fields (field (name "MPN") "BSS138W-7-F"))
      (libsource (lib "eagle-import") (part "SMD-MOSFET-N-CH-50V-200MA-BSS138W-7-F(SOT-23)"))
    )
    (comp (ref "Q2")
      (value "BA")
      (footprint "eagle-import:SOT89")
      (libsource (lib "eagle-import") (part "PNP-TRANSISTOR_SOT89"))
    )
    (comp (ref "Q3")
      (value "J1")
      (footprint "eagle-import:SOT-23")
      (fields (field (name "MPN") "BSS138W-7-F"))
      (libsource (lib "eagle-import") (part "SMD-MOSFET-N-CH-50V-200MA-BSS138W-7-F(SOT-23)"))
    )
    (comp (ref "Q101")
      (value "BA.")
      (footprint "eagle-import:SOT89")
      (libsource (lib "eagle-import") (part "PNP-TRANSISTOR_SOT89"))
    )
    (comp (ref "Q102")
      (value "BA.")
      (footprint "eagle-import:SOT89")
      (libsource (lib "eagle-import") (part "PNP-TRANSISTOR_SOT89"))
    )
    (comp (ref "Q103")
      (value "MY")
      (footprint "eagle-import:SOT89")
      (libsource (lib "eagle-import") (part "NPN-TRANSISTOR_SOT89"))
    )
    (comp (ref "Q104")
      (value "BA")
      (footprint "eagle-import:SOT89")
      (libsource (lib "eagle-import") (part "PNP-TRANSISTOR_SOT89"))
    )
    (comp (ref "Q105")
      (value "BA")
      (footprint "eagle-import:SOT89")
      (libsource (lib "eagle-import") (part "PNP-TRANSISTOR_SOT89"))
    )
    (comp (ref "Q106")
      (value "J1")
      (footprint "eagle-import:SOT-23")
      (fields (field (name "MPN") "BSS138W-7-F"))
      (libsource (lib "eagle-import") (part "SMD-MOSFET-N-CH-50V-200MA-BSS138W-7-F(SOT-23)"))
    )
    (comp (ref "Q107")
      (value "J1")
      (footprint "eagle-import:SOT-23")
      (fields (field (name "MPN") "BSS138W-7-F"))
      (libsource (lib "eagle-import") (part "SMD-MOSFET-N-CH-50V-200MA-BSS138W-7-F(SOT-23)"))
    )
    (comp (ref "R1")
      (value "104")
      (footprint "eagle-import:R0805")
      (fields (field (name "MPN") "RC0805FR-0710KL"))
      (libsource (lib "eagle-import") (part "SMD-RES-10K-1%-1/8W(0805)"))
    )
    (comp (ref "R2")
      (value "104")
      (footprint "eagle-import:R0805")
      (fields (field (name "MPN") "RC0805FR-0710KL"))
      (libsource (lib "eagle-import") (part "SMD-RES-10K-1%-1/8W(0805)"))
    )
    (comp (ref "R3")
      (value "104")
      (footprint "eagle-import:R0805")
      (fields (field (name "MPN") "RC0805FR-0710KL"))
      (libsource (lib "eagle-import") (part "SMD-RES-10K-1%-1/8W(0805)"))
    )
    (comp (ref "R4")
      (value "100")
      (footprint "eagle-import:R0805")
      (fields (field (name "MPN") "RC0805JR-07220RL"))
      (libsource (lib "eagle-import") (part "SMD-RES-220R-5%-1/8W(0805)"))
    )
    (comp (ref "R5")
      (value "13")
      (footprint "eagle-import:R1206")
      (fields (field (name "MPN") "RC1206JR-0713RL"))
      (libsource (lib "eagle-import") (part "SMD-RES-13R-5%-1/4W(1206)"))
    )
    (comp (ref "R6")
      (value "102")
      (footprint "eagle-import:R0805")
      (fields (field (name "MPN") "RC0805JR-071KL"))
      (libsource (lib "eagle-import") (part "SMD-RES-1K-5%-1/8W(0805)"))
    )
    (comp (ref "R7")
      (value "13")
      (footprint "eagle-import:R1206")
      (fields (field (name "MPN") "RC1206JR-0713RL"))
      (libsource (lib "eagle-import") (part "SMD-RES-13R-5%-1/4W(1206)"))
    )
    (comp (ref "R8")
      (value "4701")
      (footprint "eagle-import:R0805")
      (fields (field (name "MPN") "RC0805JR-074K7L"))
      (libsource (lib "eagle-import") (part "SMD-RES-4.7K-5%-1/8W(0805)"))
    )
    (comp (ref "R9")
      (value "13")
      (footprint "eagle-import:R1206")
      (fields (field (name "MPN") "RC1206JR-0713RL"))
      (libsource (lib "eagle-import") (part "SMD-RES-13R-5%-1/4W(1206)"))
    )
    (comp (ref "R10")
      (value "102")
      (footprint "eagle-import:R0805")
      (fields (field (name "MPN") "RC0805JR-071KL"))
      (libsource (lib "eagle-import") (part "SMD-RES-1K-5%-1/8W(0805)"))
    )
    (comp (ref "R11")
      (value "104")
      (footprint "eagle-import:R0805")
      (fields (field (name "MPN") "RC0805FR-0710KL"))
      (libsource (lib "eagle-import") (part "SMD-RES-10K-1%-1/8W(0805)"))
    )
    (comp (ref "R12")
      (value "102")
      (footprint "eagle-import:R0805")
      (fields (field (name "MPN") "RC0805JR-071KL"))
      (libsource (lib "eagle-import") (part "SMD-RES-1K-5%-1/8W(0805)"))
    )
    (comp (ref "R13")
      (value "100")
      (footprint "eagle-import:R0805")
      (fields (field (name "MPN") "RC0805JR-07220RL"))
      (libsource (lib "eagle-import") (part "SMD-RES-220R-5%-1/8W(0805)"))
    )
    (comp (ref "R14")
      (value "NTC")
      (footprint "eagle-import:R0805")
      (fields (field (name "MPN") "RC0805JR-071KL"))
      (libsource (lib "eagle-import") (part "SMD-RES-1K-5%-1/8W(0805)"))
    )
    (comp (ref "R101")
      (value "102")
      (footprint "eagle-import:R0805")
      (fields (field (name "MPN") "RC0805JR-071KL"))
      (libsource (lib "eagle-import") (part "SMD-RES-1K-5%-1/8W(0805)"))
    )
    (comp (ref "R102")
      (value "13")
      (footprint "eagle-import:R1206")
      (fields (field (name "MPN") "RC1206JR-0713RL"))
      (libsource (lib "eagle-import") (part "SMD-RES-13R-5%-1/4W(1206)"))
    )
    (comp (ref "R103")
      (value "R_user")
      (footprint "eagle-import:R0805")
      (libsource (lib "eagle-import") (part "R-EU_R0805"))
    )
    (comp (ref "R104")
      (value "R_user")
      (footprint "eagle-import:R0805")
      (libsource (lib "eagle-import") (part "R-EU_R0805"))
    )
    (comp (ref "R105")
      (value "4701")
      (footprint "eagle-import:R0805")
      (fields (field (name "MPN") "RC0805JR-074K7L"))
      (libsource (lib "eagle-import") (part "SMD-RES-4.7K-5%-1/8W(0805)"))
    )
    (comp (ref "R106")
      (value "13")
      (footprint "eagle-import:R1206")
      (fields (field (name "MPN") "RC1206JR-0713RL"))
      (libsource (lib "eagle-import") (part "SMD-RES-13R-5%-1/4W(1206)"))
    )
    (comp (ref "R107")
      (value "1002")
      (footprint "eagle-import:R0805")
      (fields (field (name "MPN") "RC0805FR-0710KL"))
      (libsource (lib "eagle-import") (part "SMD-RES-10K-1%-1/8W(0805)"))
    )
    (comp (ref "R108")
      (value "1002")
      (footprint "eagle-import:R0805")
      (fields (field (name "MPN") "RC0805FR-0710KL"))
      (libsource (lib "eagle-import") (part "SMD-RES-10K-1%-1/8W(0805)"))
    )
    (comp (ref "R109")
      (value "104")
      (footprint "eagle-import:R0805")
      (fields (field (name "MPN") "RC0805FR-0710KL"))
      (libsource (lib "eagle-import") (part "SMD-RES-10K-1%-1/8W(0805)"))
    )
    (comp (ref "R110")
      (value "104")
      (footprint "eagle-import:R0805")
      (fields (field (name "MPN") "RC0805FR-0710KL"))
      (libsource (lib "eagle-import") (part "SMD-RES-10K-1%-1/8W(0805)"))
    )
    (comp (ref "R111")
      (value "104")
      (footprint "eagle-import:R0805")
      (fields (field (name "MPN") "RC0805FR-0710KL"))
      (libsource (lib "eagle-import") (part "SMD-RES-10K-1%-1/8W(0805)"))
    )
    (comp (ref "R112")
      (value "102")
      (footprint "eagle-import:R0805")
      (fields (field (name "MPN") "RC0805JR-071KL"))
      (libsource (lib "eagle-import") (part "SMD-RES-1K-5%-1/8W(0805)"))
    )
    (comp (ref "R113")
      (value "102")
      (footprint "eagle-import:R0805")
      (fields (field (name "MPN") "RC0805JR-071KL"))
      (libsource (lib "eagle-import") (part "SMD-RES-1K-5%-1/8W(0805)"))
    )
    (comp (ref "R114")
      (value "102")
      (footprint "eagle-import:R0805")
      (fields (field (name "MPN") "RC0805JR-071KL"))
      (libsource (lib "eagle-import") (part "SMD-RES-1K-5%-1/8W(0805)"))
    )
    (comp (ref "R115")
      (value "100")
      (footprint "eagle-import:R0805")
      (fields (field (name "MPN") "RC0805JR-07220RL"))
      (libsource (lib "eagle-import") (part "SMD-RES-220R-5%-1/8W(0805)"))
    )
    (comp (ref "R116")
      (value "2201")
      (footprint "eagle-import:R0805")
      (fields (field (name "MPN") "RC0805JR-074K7L"))
      (libsource (lib "eagle-import") (part "SMD-RES-4.7K-5%-1/8W(0805)"))
    )
    (comp (ref "R117")
      (value "2702")
      (footprint "eagle-import:R0805")
      (fields (field (name "MPN") "RC0805JR-074K7L"))
      (libsource (lib "eagle-import") (part "SMD-RES-4.7K-5%-1/8W(0805)"))
    )
    (comp (ref "R119")
      (value "2201")
      (footprint "eagle-import:R0805")
      (fields (field (name "MPN") "RC0805JR-072K2L"))
      (libsource (lib "eagle-import") (part "SMD-RES-2.2K-5%-1/8W(0805)"))
    )
    (comp (ref "R120")
      (value "1002")
      (footprint "eagle-import:R0805")
      (fields (field (name "MPN") "RC0805FR-0710KL"))
      (libsource (lib "eagle-import") (part "SMD-RES-10K-1%-1/8W(0805)"))
    )
    (comp (ref "R121")
      (value "1502")
      (footprint "eagle-import:R0805")
      (fields (field (name "MPN") "RC0805FR-0710KL"))
      (libsource (lib "eagle-import") (part "SMD-RES-10K-1%-1/8W(0805)"))
    )
    (comp (ref "R122")
      (value "2702")
      (footprint "eagle-import:R0805")
      (fields (field (name "MPN") "RC0805JR-074K7L"))
      (libsource (lib "eagle-import") (part "SMD-RES-4.7K-5%-1/8W(0805)"))
    )
    (comp (ref "R123")
      (value "2702")
      (footprint "eagle-import:R0805")
      (fields (field (name "MPN") "RC0805JR-074K7L"))
      (libsource (lib "eagle-import") (part "SMD-RES-4.7K-5%-1/8W(0805)"))
    )
    (comp (ref "R124")
      (value "1002")
      (footprint "eagle-import:R0805")
      (fields (field (name "MPN") "RC0805FR-0710KL"))
      (libsource (lib "eagle-import") (part "SMD-RES-10K-1%-1/8W(0805)"))
    )
    (comp (ref "R125")
      (value "104")
      (footprint "eagle-import:R0805")
      (fields (field (name "MPN") "RC0805FR-0710KL"))
      (libsource (lib "eagle-import") (part "SMD-RES-10K-1%-1/8W(0805)"))
    )
    (comp (ref "R126")
      (value "4701")
      (footprint "eagle-import:R0805")
      (fields (field (name "MPN") "RC0805JR-074K7L"))
      (libsource (lib "eagle-import") (part "SMD-RES-4.7K-5%-1/8W(0805)"))
    )
    (comp (ref "R127")
      (value "47")
      (footprint "eagle-import:V235_17_1MM")
      (libsource (lib "eagle-import") (part "R-EU_V235/17_1MM"))
    )
    (comp (ref "R128")
      (value "102")
      (footprint "eagle-import:R0805")
      (fields (field (name "MPN") "RC0805JR-071KL"))
      (libsource (lib "eagle-import") (part "SMD-RES-1K-5%-1/8W(0805)"))
    )
    (comp (ref "R129")
      (value "47")
      (footprint "eagle-import:V235_17_1MM")
      (libsource (lib "eagle-import") (part "R-EU_V235/17_1MM"))
    )
    (comp (ref "R130")
      (value "104")
      (footprint "eagle-import:R0805")
      (fields (field (name "MPN") "RC0805FR-0710KL"))
      (libsource (lib "eagle-import") (part "SMD-RES-10K-1%-1/8W(0805)"))
    )
    (comp (ref "R131")
      (value "1502")
      (footprint "eagle-import:R0805")
      (fields (field (name "MPN") "RC0805FR-0710KL"))
      (libsource (lib "eagle-import") (part "SMD-RES-10K-1%-1/8W(0805)"))
    )
    (comp (ref "R132")
      (value "1002")
      (footprint "eagle-import:R0805")
      (fields (field (name "MPN") "RC0805FR-0710KL"))
      (libsource (lib "eagle-import") (part "SMD-RES-10K-1%-1/8W(0805)"))
    )
    (comp (ref "R133")
      (value "2201")
      (footprint "eagle-import:R0805")
      (fields (field (name "MPN") "RC0805JR-072K2L"))
      (libsource (lib "eagle-import") (part "SMD-RES-2.2K-5%-1/8W(0805)"))
    )
    (comp (ref "R134")
      (value "13")
      (footprint "eagle-import:R1206")
      (fields (field (name "MPN") "RC1206JR-0713RL"))
      (libsource (lib "eagle-import") (part "SMD-RES-13R-5%-1/4W(1206)"))
    )
    (comp (ref "R135")
      (value "104")
      (footprint "eagle-import:R0805")
      (fields (field (name "MPN") "RC0805FR-0710KL"))
      (libsource (lib "eagle-import") (part "SMD-RES-10K-1%-1/8W(0805)"))
    )
    (comp (ref "R136")
      (value "47")
      (footprint "eagle-import:V235_17_1MM")
      (libsource (lib "eagle-import") (part "R-EU_V235/17_1MM"))
    )
    (comp (ref "R137")
      (value "47")
      (footprint "eagle-import:V235_17_1MM")
      (libsource (lib "eagle-import") (part "R-EU_V235/17_1MM"))
    )
    (comp (ref "R138")
      (value "100")
      (footprint "eagle-import:R0805")
      (fields (field (name "MPN") "RC0805JR-072K2L"))
      (libsource (lib "eagle-import") (part "SMD-RES-2.2K-5%-1/8W(0805)"))
    )
    (comp (ref "R140")
      (value "2702")
      (footprint "eagle-import:R0805")
      (fields (field (name "MPN") "RC0805FR-0710KL"))
      (libsource (lib "eagle-import") (part "SMD-RES-10K-1%-1/8W(0805)"))
    )
    (comp (ref "R141")
      (value "104")
      (footprint "eagle-import:R0805")
      (fields (field (name "MPN") "RC0805FR-0710KL"))
      (libsource (lib "eagle-import") (part "SMD-RES-10K-1%-1/8W(0805)"))
    )
    (comp (ref "R142")
      (value "(1000)")
      (footprint "eagle-import:R0805")
      (fields (field (name "MPN") "RC0805JR-07100RL"))
      (libsource (lib "eagle-import") (part "SMD-RES-100R-5%-1/8W(0805)"))
    )
    (comp (ref "R143")
      (value "(101)")
      (footprint "eagle-import:R0805")
      (fields (field (name "MPN") "RC0805JR-07100RL"))
      (libsource (lib "eagle-import") (part "SMD-RES-100R-5%-1/8W(0805)"))
    )
    (comp (ref "R144")
      (value "(1002)")
      (footprint "eagle-import:R0805")
      (fields (field (name "MPN") "RC0805FR-0710KL"))
      (libsource (lib "eagle-import") (part "SMD-RES-10K-1%-1/8W(0805)"))
    )
    (comp (ref "R145")
      (value "2702")
      (footprint "eagle-import:R0805")
      (fields (field (name "MPN") "RC0805JR-074K7L"))
      (libsource (lib "eagle-import") (part "SMD-RES-4.7K-5%-1/8W(0805)"))
    )
    (comp (ref "R146")
      (value "(1002)")
      (footprint "eagle-import:R0805")
      (fields (field (name "MPN") "RC0805JR-074K7L"))
      (libsource (lib "eagle-import") (part "SMD-RES-4.7K-5%-1/8W(0805)"))
    )
    (comp (ref "SJ101")
      (value "SJ")
      (footprint "eagle-import:SJ")
      (libsource (lib "eagle-import") (part "SJ"))
    )
    (comp (ref "START")
      (value "TPSB2.0")
      (footprint "eagle-import:B2.0")
      (libsource (lib "eagle-import") (part "TPSB2.0"))
    )
    (comp (ref "TP1")
      (value "TPSB2.0")
      (footprint "eagle-import:B2.0")
      (libsource (lib "eagle-import") (part "TPSB2.0"))
    )
    (comp (ref "TP2")
      (value "TPSB2.0")
      (footprint "eagle-import:B2.0")
      (libsource (lib "eagle-import") (part "TPSB2.0"))
    )
    (comp (ref "TP3")
      (value "TPSB2.0")
      (footprint "eagle-import:B2.0")
      (libsource (lib "eagle-import") (part "TPSB2.0"))
    )
    (comp (ref "TP4")
      (value "TPSB2.0")
      (footprint "eagle-import:B2.0")
      (libsource (lib "eagle-import") (part "TPSB2.0"))
    )
    (comp (ref "TP5")
      (value "TPSB2.0")
      (footprint "eagle-import:B2.0")
      (libsource (lib "eagle-import") (part "TPSB2.0"))
    )
    (comp (ref "TP6")
      (value "TPSB2.0")
      (footprint "eagle-import:B2.0")
      (libsource (lib "eagle-import") (part "TPSB2.0"))
    )
    (comp (ref "TP7")
      (value "TPSB2.0")
      (footprint "eagle-import:B2.0")
      (libsource (lib "eagle-import") (part "TPSB2.0"))
    )
    (comp (ref "TP8")
      (value "TPSB2.0")
      (footprint "eagle-import:B2.0")
      (libsource (lib "eagle-import") (part "TPSB2.0"))
    )
    (comp (ref "TP9")
      (value "TPSB2.0")
      (footprint "eagle-import:B2.0")
      (libsource (lib "eagle-import") (part "TPSB2.0"))
    )
    (comp (ref "TP10")
      (value "TPSB2.0")
      (footprint "eagle-import:B2.0")
      (libsource (lib "eagle-import") (part "TPSB2.0"))
    )
    (comp (ref "TP11")
      (value "TPSB2.0")
      (footprint "eagle-import:B2.0")
      (libsource (lib "eagle-import") (part "TPSB2.0"))
    )
    (comp (ref "TP12")
      (value "TPSB2.0")
      (footprint "eagle-import:B2.0")
      (libsource (lib "eagle-import") (part "TPSB2.0"))
    )
    (comp (ref "TP13")
      (value "TPSB2.0")
      (footprint "eagle-import:B2.0")
      (libsource (lib "eagle-import") (part "TPSB2.0"))
    )
    (comp (ref "TP16")
      (value "TPSB2.0")
      (footprint "eagle-import:B2.0")
      (libsource (lib "eagle-import") (part "TPSB2.0"))
    )
    (comp (ref "TP17")
      (value "TPSB2.0")
      (footprint "eagle-import:B2.0")
      (libsource (lib "eagle-import") (part "TPSB2.0"))
    )
    (comp (ref "TP18")
      (value "TPSB2.0")
      (footprint "eagle-import:B2.0")
      (libsource (lib "eagle-import") (part "TPSB2.0"))
    )
    (comp (ref "TP19")
      (value "TPSB2.0")
      (footprint "eagle-import:B2.0")
      (libsource (lib "eagle-import") (part "TPSB2.0"))
    )
    (comp (ref "TP21")
      (value "TPSB2.0")
      (footprint "eagle-import:B2.0")
      (libsource (lib "eagle-import") (part "TPSB2.0"))
    )
    (comp (ref "TP22")
      (value "TPSB2.0")
      (footprint "eagle-import:B2.0")
      (libsource (lib "eagle-import") (part "TPSB2.0"))
    )
    (comp (ref "TP23")
      (value "TPSB2.0")
      (footprint "eagle-import:B2.0")
      (libsource (lib "eagle-import") (part "TPSB2.0"))
    )
    (comp (ref "TP24")
      (value "TPSB1,27")
      (footprint "eagle-import:B1,27")
      (libsource (lib "eagle-import") (part "TPSB1,27"))
    )
    (comp (ref "TP25")
      (value "TPSB2.0")
      (footprint "eagle-import:B2.0")
      (libsource (lib "eagle-import") (part "TPSB2.0"))
    )
    (comp (ref "TP26")
      (value "TPSB2.0")
      (footprint "eagle-import:B2.0")
      (libsource (lib "eagle-import") (part "TPSB2.0"))
    )
    (comp (ref "X101")
      (value "CON_BMWV2")
      (footprint "eagle-import:24-PIN_V2")
      (libsource (lib "eagle-import") (part "CON_BMWV2"))
    )
    (comp (ref "X102")
      (value "22-23-2021")
      (footprint "eagle-import:22-23-2021")
      (fields (field (name "MF") "MOLEX"))
      (libsource (lib "eagle-import") (part "22-23-2021"))
    )
    (comp (ref "X103")
      (value "22-23-2051")
      (footprint "eagle-import:22-23-2051")
      (fields (field (name "MF") "MOLEX"))
      (libsource (lib "eagle-import") (part "22-23-2051"))
    )
  )
  (nets
    (net (code "1") (name "+10V") (class "Default")
      (node (ref "10V") (pin "TP") (pinfunction "PP_TP") (pintype "input"))
      (node (ref "10V1") (pin "TP") (pinfunction "PP_TP") (pintype "input"))
      (node (ref "C10") (pin "1") (pinfunction "1_1") (pintype "passive"))
      (node (ref "C102") (pin "1") (pinfunction "1_1") (pintype "passive"))
      (node (ref "IC1") (pin "8") (pinfunction "V+_8") (pintype "power_in"))
      (node (ref "IC10") (pin "1") (pinfunction "OUT_1") (pintype "passive"))
      (node (ref "IC104") (pin "1") (pinfunction "OUT_1") (pintype "passive"))
      (node (ref "IC110") (pin "4") (pinfunction "R_4") (pintype "input"))
      (node (ref "IC110") (pin "8") (pinfunction "V+_8") (pintype "power_in"))
      (node (ref "IC111") (pin "13") (pinfunction "CD_13") (pintype "input"))
      (node (ref "IC111") (pin "16") (pinfunction "VDD_16") (pintype "power_in"))
      (node (ref "IC111") (pin "3") (pinfunction "CD_3") (pintype "input"))
      (node (ref "IC111") (pin "5") (pinfunction "B_5") (pintype "input"))
      (node (ref "IC12") (pin "8") (pinfunction "V+_8") (pintype "power_in"))
      (node (ref "IC8") (pin "4") (pinfunction "R_4") (pintype "input"))
      (node (ref "IC8") (pin "8") (pinfunction "V+_8") (pintype "power_in"))
      (node (ref "IC9") (pin "13") (pinfunction "CD_13") (pintype "input"))
      (node (ref "IC9") (pin "16") (pinfunction "VDD_16") (pintype "power_in"))
      (node (ref "IC9") (pin "3") (pinfunction "CD_3") (pintype "input"))
      (node (ref "IC9") (pin "5") (pinfunction "B_5") (pintype "input"))
      (node (ref "R11") (pin "1") (pinfunction "1_1") (pintype "passive"))
      (node (ref "R12") (pin "1") (pinfunction "1_1") (pintype "passive"))
      (node (ref "R145") (pin "2") (pinfunction "2_2") (pintype "passive"))
      (node (ref "R50") (pin "2") (pinfunction "2_2") (pintype "passive"))
      (node (ref "R69") (pin "1") (pinfunction "1_1") (pintype "passive"))
      (node (ref "R70") (pin "1") (pinfunction "1_1") (pintype "passive"))
    )
    (net (code "2") (name "+12V") (class "Default")
      (node (ref "2") (pin "1") (pinfunction "KL_1") (pintype "passive"))
      (node (ref "4") (pin "1") (pinfunction "KL_1") (pintype "passive"))
      (node (ref "C1") (pin "1") (pinfunction "1_1") (pintype "passive"))
      (node (ref "C13") (pin "1") (pinfunction "1_1") (pintype "passive"))
      (node (ref "D101") (pin "C") (pinfunction "C_C") (pintype "passive"))
      (node (ref "D13") (pin "C") (pinfunction "C_C") (pintype "passive"))
      (node (ref "IC10") (pin "3") (pinfunction "IN_3") (pintype "input"))
      (node (ref "IC102") (pin "3") (pinfunction "IN_3") (pintype "input"))
      (node (ref "IC103") (pin "IN") (pinfunction "IN_IN") (pintype "input"))
      (node (ref "IC104") (pin "3") (pinfunction "IN_3") (pintype "input"))
      (node (ref "IC105") (pin "16") (pinfunction "VDD_16") (pintype "power_in"))
      (node (ref "IC107") (pin "9") (pinfunction "CD+_9") (pintype "passive"))
      (node (ref "IC2") (pin "16") (pinfunction "VDD_16") (pintype "power_in"))
      (node (ref "IC3") (pin "IN") (pinfunction "IN_IN") (pintype "input"))
      (node (ref "IC5") (pin "9") (pinfunction "CD+_9") (pintype "passive"))
      (node (ref "IC7") (pin "3") (pinfunction "IN_3") (pintype "input"))
      (node (ref "JP1") (pin "2") (pinfunction "2_2") (pintype "passive"))
      (node (ref "JP101") (pin "2") (pinfunction "2_2") (pintype "passive"))
      (node (ref "R102") (pin "1") (pinfunction "1_1") (pintype "passive"))
      (node (ref "R106") (pin "1") (pinfunction "1_1") (pintype "passive"))
      (node (ref "R109") (pin "2") (pinfunction "2_2") (pintype "passive"))
      (node (ref "R110") (pin "2") (pinfunction "2_2") (pintype "passive"))
      (node (ref "R111") (pin "2") (pinfunction "2_2") (pintype "passive"))
      (node (ref "R135") (pin "1") (pinfunction "1_1") (pintype "passive"))
      (node (ref "R18") (pin "2") (pinfunction "2_2") (pintype "passive"))
      (node (ref "R19") (pin "2") (pinfunction "2_2") (pintype "passive"))
      (node (ref "R20") (pin "2") (pinfunction "2_2") (pintype "passive"))
      (node (ref "R39") (pin "1") (pinfunction "1_1") (pintype "passive"))
      (node (ref "R40") (pin "1") (pinfunction "1_1") (pintype "passive"))
      (node (ref "R44") (pin "1") (pinfunction "1_1") (pintype "passive"))
      (node (ref "R64") (pin "2") (pinfunction "2_2") (pintype "passive"))
      (node (ref "R7") (pin "2") (pinfunction "2_2") (pintype "passive"))
      (node (ref "TP12") (pin "TP") (pinfunction "PP_TP") (pintype "input"))
      (node (ref "TP45") (pin "TP") (pinfunction "PP_TP") (pintype "input"))
      (node (ref "X103") (pin "1") (pinfunction "S_1") (pintype "passive"))
      (node (ref "X2") (pin "1") (pinfunction "S_1") (pintype "passive"))
    )
    (net (code "3") (name "GND") (class "Default")
      (node (ref "1") (pin "12") (pinfunction "KL_12") (pintype "passive"))
      (node (ref "3") (pin "12") (pinfunction "KL_12") (pintype "passive"))
      (node (ref "C1") (pin "2") (pinfunction "2_2") (pintype "passive"))
      (node (ref "C10") (pin "2") (pinfunction "2_2") (pintype "passive"))
      (node (ref "C101") (pin "2") (pinfunction "2_2") (pintype "passive"))
      (node (ref "C102") (pin "2") (pinfunction "2_2") (pintype "passive"))
      (node (ref "C103") (pin "2") (pinfunction "2_2") (pintype "passive"))
      (node (ref "C104") (pin "2") (pinfunction "2_2") (pintype "passive"))
      (node (ref "C105") (pin "2") (pinfunction "2_2") (pintype "passive"))
      (node (ref "C106") (pin "1") (pinfunction "1_1") (pintype "passive"))
      (node (ref "C107") (pin "2") (pinfunction "2_2") (pintype "passive"))
      (node (ref "C108") (pin "2") (pinfunction "2_2") (pintype "passive"))
      (node (ref "C109") (pin "1") (pinfunction "1_1") (pintype "passive"))
      (node (ref "C11") (pin "2") (pinfunction "2_2") (pintype "passive"))
      (node (ref "C110") (pin "2") (pinfunction "2_2") (pintype "passive"))
      (node (ref "C12") (pin "2") (pinfunction "2_2") (pintype "passive"))
      (node (ref "C13") (pin "2") (pinfunction "2_2") (pintype "passive"))
      (node (ref "C14") (pin "1") (pinfunction "1_1") (pintype "passive"))
      (node (ref "C2") (pin "1") (pinfunction "1_1") (pintype "passive"))
      (node (ref "C3") (pin "2") (pinfunction "2_2") (pintype "passive"))
      (node (ref "C4") (pin "2") (pinfunction "2_2") (pintype "passive"))
      (node (ref "C5") (pin "2") (pinfunction "2_2") (pintype "passive"))
      (node (ref "C6") (pin "2") (pinfunction "2_2") (pintype "passive"))
      (node (ref "C7") (pin "2") (pinfunction "2_2") (pintype "passive"))
      (node (ref "C8") (pin "1") (pinfunction "1_1") (pintype "passive"))
      (node (ref "C9") (pin "1") (pinfunction "1_1") (pintype "passive"))
      (node (ref "D101") (pin "A") (pinfunction "A_A") (pintype "passive"))
      (node (ref "D104") (pin "A") (pinfunction "A_A") (pintype "passive"))
      (node (ref "D105") (pin "1") (pinfunction "+_1") (pintype "passive"))
      (node (ref "D11") (pin "1") (pinfunction "+_1") (pintype "passive"))
      (node (ref "D13") (pin "A") (pinfunction "A_A") (pintype "passive"))
      (node (ref "D14") (pin "A") (pinfunction "A_A") (pintype "passive"))
      (node (ref "D17") (pin "2") (pinfunction "A_2") (pintype "passive"))
      (node (ref "D4") (pin "2") (pinfunction "A_2") (pintype "passive"))
      (node (ref "IC1") (pin "1") (pinfunction "GND_1") (pintype "passive"))
      (node (ref "IC1") (pin "4") (pinfunction "V-_4") (pintype "power_in"))
      (node (ref "IC10") (pin "2") (pinfunction "GND_2") (pintype "input"))
      (node (ref "IC10") (pin "2@1") (pinfunction "GND_2@1") (pintype "input"))
      (node (ref "IC101") (pin "4") (pinfunction "V-_4") (pintype "power_in"))
      (node (ref "IC102") (pin "2") (pinfunction "GND_2") (pintype "input"))
      (node (ref "IC102") (pin "2@1") (pinfunction "GND_2@1") (pintype "input"))
      (node (ref "IC103") (pin "GND") (pinfunction "GND_GND") (pintype "input"))
      (node (ref "IC104") (pin "2") (pinfunction "GND_2") (pintype "input"))
      (node (ref "IC104") (pin "2@1") (pinfunction "GND_2@1") (pintype "input"))
      (node (ref "IC105") (pin "11") (pinfunction "D_11") (pintype "input"))
      (node (ref "IC105") (pin "8") (pinfunction "VSS_8") (pintype "power_in"))
      (node (ref "IC107") (pin "8") (pinfunction "GND_8") (pintype "power_in"))
      (node (ref "IC108") (pin "12") (pinfunction "GND_12") (pintype "power_in"))
      (node (ref "IC11") (pin "4") (pinfunction "V-_4") (pintype "power_in"))
      (node (ref "IC110") (pin "1") (pinfunction "GND_1") (pintype "power_in"))
      (node (ref "IC111") (pin "1") (pinfunction "T1_1") (pintype "input"))
      (node (ref "IC111") (pin "15") (pinfunction "T1_15") (pintype "input"))
      (node (ref "IC111") (pin "4") (pinfunction "A_4") (pintype "input"))
      (node (ref "IC111") (pin "8") (pinfunction "VSS_8") (pintype "power_in"))
      (node (ref "IC12") (pin "1") (pinfunction "GND_1") (pintype "passive"))
      (node (ref "IC12") (pin "4") (pinfunction "V-_4") (pintype "power_in"))
      (node (ref "IC2") (pin "11") (pinfunction "D_11") (pintype "input"))
      (node (ref "IC2") (pin "8") (pinfunction "VSS_8") (pintype "power_in"))
      (node (ref "IC3") (pin "GND") (pinfunction "GND_GND") (pintype "input"))
      (node (ref "IC5") (pin "8") (pinfunction "GND_8") (pintype "power_in"))
      (node (ref "IC6") (pin "12") (pinfunction "GND_12") (pintype "power_in"))
      (node (ref "IC7") (pin "2") (pinfunction "GND_2") (pintype "input"))
      (node (ref "IC7") (pin "2@1") (pinfunction "GND_2@1") (pintype "input"))
      (node (ref "IC8") (pin "1") (pinfunction "GND_1") (pintype "power_in"))
      (node (ref "IC9") (pin "1") (pinfunction "T1_1") (pintype "input"))
      (node (ref "IC9") (pin "15") (pinfunction "T1_15") (pintype "input"))
      (node (ref "IC9") (pin "4") (pinfunction "A_4") (pintype "input"))
      (node (ref "IC9") (pin "8") (pinfunction "VSS_8") (pintype "power_in"))
      (node (ref "PAD3") (pin "1") (pinfunction "P_1") (pintype "passive"))
      (node (ref "PAD6") (pin "1") (pinfunction "P_1") (pintype "passive"))
      (node (ref "Q1") (pin "2") (pinfunction "S_2") (pintype "passive"))
      (node (ref "Q107") (pin "2") (pinfunction "S_2") (pintype "passive"))
      (node (ref "Q11") (pin "2") (pinfunction "S_2") (pintype "passive"))
      (node (ref "Q13") (pin "2") (pinfunction "S_2") (pintype "passive"))
      (node (ref "Q3") (pin "2") (pinfunction "S_2") (pintype "passive"))
      (node (ref "Q9") (pin "2") (pinfunction "S_2") (pintype "passive"))
      (node (ref "R101") (pin "2") (pinfunction "2_2") (pintype "passive"))
      (node (ref "R103") (pin "2") (pinfunction "2_2") (pintype "passive"))
      (node (ref "R104") (pin "2") (pinfunction "2_2") (pintype "passive"))
      (node (ref "R107") (pin "1") (pinfunction "1_1") (pintype "passive"))
      (node (ref "R114") (pin "1") (pinfunction "1_1") (pintype "passive"))
      (node (ref "R123") (pin "1") (pinfunction "1_1") (pintype "passive"))
      (node (ref "R132") (pin "1") (pinfunction "1_1") (pintype "passive"))
      (node (ref "R136") (pin "1") (pinfunction "1_1") (pintype "passive"))
      (node (ref "R137") (pin "1") (pinfunction "1_1") (pintype "passive"))
      (node (ref "R14") (pin "2") (pinfunction "2_2") (pintype "passive"))
      (node (ref "R141") (pin "2") (pinfunction "2_2") (pintype "passive"))
      (node (ref "R143") (pin "2") (pinfunction "2_2") (pintype "passive"))
      (node (ref "R22") (pin "1") (pinfunction "1_1") (pintype "passive"))
      (node (ref "R28") (pin "1") (pinfunction "1_1") (pintype "passive"))
      (node (ref "R32") (pin "1") (pinfunction "1_1") (pintype "passive"))
      (node (ref "R33") (pin "2") (pinfunction "2_2") (pintype "passive"))
      (node (ref "R34") (pin "2") (pinfunction "2_2") (pintype "passive"))
      (node (ref "R36") (pin "2") (pinfunction "2_2") (pintype "passive"))
      (node (ref "R4") (pin "1") (pinfunction "1_1") (pintype "passive"))
      (node (ref "R45") (pin "2") (pinfunction "2_2") (pintype "passive"))
      (node (ref "R48") (pin "1") (pinfunction "1_1") (pintype "passive"))
      (node (ref "R49") (pin "1") (pinfunction "1_1") (pintype "passive"))
      (node (ref "R5") (pin "2") (pinfunction "2_2") (pintype "passive"))
      (node (ref "R57") (pin "1") (pinfunction "1_1") (pintype "passive"))
      (node (ref "R58") (pin "2") (pinfunction "2_2") (pintype "passive"))
      (node (ref "R6") (pin "2") (pinfunction "2_2") (pintype "passive"))
      (node (ref "R62") (pin "2") (pinfunction "2_2") (pintype "passive"))
      (node (ref "R63") (pin "2") (pinfunction "2_2") (pintype "passive"))
      (node (ref "R65") (pin "1") (pinfunction "1_1") (pintype "passive"))
      (node (ref "R72") (pin "2") (pinfunction "2_2") (pintype "passive"))
      (node (ref "X1") (pin "13") (pinfunction "13_13") (pintype "passive"))
      (node (ref "X1") (pin "18") (pinfunction "18_18") (pintype "passive"))
      (node (ref "X1") (pin "23") (pinfunction "23_23") (pintype "passive"))
      (node (ref "X101") (pin "13") (pinfunction "13_13") (pintype "passive"))
      (node (ref "X101") (pin "18") (pinfunction "18_18") (pintype "passive"))
      (node (ref "X101") (pin "23") (pinfunction "23_23") (pintype "passive"))
      (node (ref "X102") (pin "1") (pinfunction "S_1") (pintype "passive"))
      (node (ref "X103") (pin "5") (pinfunction "S_5") (pintype "passive"))
      (node (ref "X2") (pin "5") (pinfunction "S_5") (pintype "passive"))
      (node (ref "X3") (pin "1") (pinfunction "S_1") (pintype "passive"))
    )
    (net (code "4") (name "Net-(1A-KL)") (class "Default")
      (node (ref "1") (pin "1") (pinfunction "KL_1") (pintype "passive"))
      (node (ref "D2") (pin "2") (pinfunction "-_2") (pintype "passive"))
      (node (ref "R13") (pin "2") (pinfunction "2_2") (pintype "passive"))
      (node (ref "TP1") (pin "TP") (pinfunction "PP_TP") (pintype "input"))
    )
    (net (code "5") (name "Net-(1B-KL)") (class "Default")
      (node (ref "1") (pin "10") (pinfunction "KL_10") (pintype "passive"))
      (node (ref "D102") (pin "2") (pinfunction "-_2") (pintype "passive"))
      (node (ref "D103") (pin "2") (pinfunction "-_2") (pintype "passive"))
      (node (ref "JP104") (pin "1") (pinfunction "1_1") (pintype "passive"))
      (node (ref "SJ101") (pin "1") (pinfunction "1_1") (pintype "passive"))
      (node (ref "TP10") (pin "TP") (pinfunction "PP_TP") (pintype "input"))
    )
    (net (code "6") (name "Net-(1C-KL)") (class "Default")
      (node (ref "1") (pin "11") (pinfunction "KL_11") (pintype "passive"))
      (node (ref "D103") (pin "1") (pinfunction "+_1") (pintype "passive"))
      (node (ref "TP11") (pin "TP") (pinfunction "PP_TP") (pintype "input"))
      (node (ref "X101") (pin "19") (pinfunction "19_19") (pintype "passive"))
    )
    (net (code "7") (name "Net-(1E-KL)") (class "Default")
      (node (ref "1") (pin "2") (pinfunction "KL_2") (pintype "passive"))
      (node (ref "Q101") (pin "2") (pinfunction "C_2") (pintype "passive"))
      (node (ref "TP2") (pin "TP") (pinfunction "PP_TP") (pintype "input"))
    )
    (net (code "8") (name "Net-(1F-KL)") (class "Default")
      (node (ref "1") (pin "3") (pinfunction "KL_3") (pintype "passive"))
      (node (ref "IC107") (pin "11") (pinfunction "O6_11") (pintype "open_collector"))
      (node (ref "TP3") (pin "TP") (pinfunction "PP_TP") (pintype "input"))
    )
    (net (code "9") (name "Net-(1G-KL)") (class "Default")
      (node (ref "1") (pin "4") (pinfunction "KL_4") (pintype "passive"))
      (node (ref "IC107") (pin "10") (pinfunction "O7_10") (pintype "open_collector"))
      (node (ref "TP4") (pin "TP") (pinfunction "PP_TP") (pintype "input"))
    )
    (net (code "10") (name "Net-(1H-KL)") (class "Default")
      (node (ref "1") (pin "5") (pinfunction "KL_5") (pintype "passive"))
      (node (ref "IC107") (pin "12") (pinfunction "O5_12") (pintype "open_collector"))
      (node (ref "TP5") (pin "TP") (pinfunction "PP_TP") (pintype "input"))
    )
    (net (code "11") (name "Net-(1I-KL)") (class "Default")
      (node (ref "1") (pin "6") (pinfunction "KL_6") (pintype "passive"))
      (node (ref "IC107") (pin "13") (pinfunction "O4_13") (pintype "open_collector"))
      (node (ref "TP6") (pin "TP") (pinfunction "PP_TP") (pintype "input"))
    )
    (net (code "12") (name "Net-(1J-KL)") (class "Default")
      (node (ref "1") (pin "7") (pinfunction "KL_7") (pintype "passive"))
      (node (ref "IC107") (pin "14") (pinfunction "O3_14") (pintype "open_collector"))
      (node (ref "TP7") (pin "TP") (pinfunction "PP_TP") (pintype "input"))
    )
    (net (code "13") (name "Net-(1K-KL)") (class "Default")
      (node (ref "1") (pin "8") (pinfunction "KL_8") (pintype "passive"))
      (node (ref "R9") (pin "2") (pinfunction "2_2") (pintype "passive"))
      (node (ref "TP8") (pin "TP") (pinfunction "PP_TP") (pintype "input"))
    )
    (net (code "14") (name "Net-(1L-KL)") (class "Default")
      (node (ref "1") (pin "9") (pinfunction "KL_9") (pintype "passive"))
      (node (ref "D102") (pin "1") (pinfunction "+_1") (pintype "passive"))
      (node (ref "TP9") (pin "TP") (pinfunction "PP_TP") (pintype "input"))
      (node (ref "X101") (pin "17") (pinfunction "17_17") (pintype "passive"))
    )
    (net (code "15") (name "Net-(2B-KL)") (class "Default")
      (node (ref "2") (pin "10") (pinfunction "KL_10") (pintype "passive"))
      (node (ref "TP25") (pin "TP") (pinfunction "PP_TP") (pintype "input"))
      (node (ref "X101") (pin "15") (pinfunction "15_15") (pintype "passive"))
    )
    (net (code "16") (name "Net-(2C-KL)") (class "Default")
      (node (ref "2") (pin "11") (pinfunction "KL_11") (pintype "passive"))
      (node (ref "Q103") (pin "2") (pinfunction "C_2") (pintype "passive"))
      (node (ref "R115") (pin "2") (pinfunction "2_2") (pintype "passive"))
      (node (ref "R119") (pin "1") (pinfunction "1_1") (pintype "passive"))
      (node (ref "TP26") (pin "TP") (pinfunction "PP_TP") (pintype "input"))
    )
    (net (code "17") (name "Net-(2D-KL)") (class "Default")
      (node (ref "2") (pin "12") (pinfunction "KL_12") (pintype "passive"))
      (node (ref "R146") (pin "1") (pinfunction "1_1") (pintype "passive"))
      (node (ref "TP13") (pin "TP") (pinfunction "PP_TP") (pintype "input"))
    )
    (net (code "18") (name "Net-(2E-KL)") (class "Default")
      (node (ref "2") (pin "2") (pinfunction "KL_2") (pintype "passive"))
      (node (ref "D109") (pin "2") (pinfunction "-_2") (pintype "passive"))
      (node (ref "LED102") (pin "K") (pinfunction "C_K") (pintype "passive"))
      (node (ref "TP16") (pin "TP") (pinfunction "PP_TP") (pintype "input"))
      (node (ref "X101") (pin "12") (pinfunction "12_12") (pintype "passive"))
    )
    (net (code "19") (name "Net-(2F-KL)") (class "Default")
      (node (ref "2") (pin "3") (pinfunction "KL_3") (pintype "passive"))
      (node (ref "D108") (pin "2") (pinfunction "-_2") (pintype "passive"))
      (node (ref "LED103") (pin "K") (pinfunction "C_K") (pintype "passive"))
      (node (ref "TP17") (pin "TP") (pinfunction "PP_TP") (pintype "input"))
      (node (ref "X101") (pin "11") (pinfunction "11_11") (pintype "passive"))
    )
    (net (code "20") (name "Net-(2G-KL)") (class "Default")
      (node (ref "2") (pin "4") (pinfunction "KL_4") (pintype "passive"))
      (node (ref "D107") (pin "2") (pinfunction "-_2") (pintype "passive"))
      (node (ref "LED104") (pin "K") (pinfunction "C_K") (pintype "passive"))
      (node (ref "TP18") (pin "TP") (pinfunction "PP_TP") (pintype "input"))
      (node (ref "X101") (pin "10") (pinfunction "10_10") (pintype "passive"))
    )
    (net (code "21") (name "Net-(2H-KL)") (class "Default")
      (node (ref "2") (pin "5") (pinfunction "KL_5") (pintype "passive"))
      (node (ref "D106") (pin "2") (pinfunction "-_2") (pintype "passive"))
      (node (ref "LED105") (pin "K") (pinfunction "C_K") (pintype "passive"))
      (node (ref "TP19") (pin "TP") (pinfunction "PP_TP") (pintype "input"))
      (node (ref "X101") (pin "9") (pinfunction "9_9") (pintype "passive"))
    )
    (net (code "22") (name "Net-(2I-KL)") (class "Default")
      (node (ref "2") (pin "6") (pinfunction "KL_6") (pintype "passive"))
      (node (ref "JP105") (pin "2") (pinfunction "2_2") (pintype "passive"))
      (node (ref "TP21") (pin "TP") (pinfunction "PP_TP") (pintype "input"))
    )
    (net (code "23") (name "Net-(2J-KL)") (class "Default")
      (node (ref "2") (pin "7") (pinfunction "KL_7") (pintype "passive"))
      (node (ref "LED101") (pin "A") (pinfunction "A_A") (pintype "passive"))
      (node (ref "TP22") (pin "TP") (pinfunction "PP_TP") (pintype "input"))
      (node (ref "X101") (pin "8") (pinfunction "8_8") (pintype "passive"))
    )
    (net (code "24") (name "Net-(2K-KL)") (class "Default")
      (node (ref "2") (pin "8") (pinfunction "KL_8") (pintype "passive"))
      (node (ref "D110") (pin "2") (pinfunction "-_2") (pintype "passive"))
      (node (ref "LED106") (pin "K") (pinfunction "C_K") (pintype "passive"))
      (node (ref "TP23") (pin "TP") (pinfunction "PP_TP") (pintype "input"))
      (node (ref "X101") (pin "14") (pinfunction "14_14") (pintype "passive"))
    )
    (net (code "25") (name "Net-(2L-KL)") (class "Default")
      (node (ref "2") (pin "9") (pinfunction "KL_9") (pintype "passive"))
      (node (ref "D107") (pin "1") (pinfunction "+_1") (pintype "passive"))
      (node (ref "D108") (pin "1") (pinfunction "+_1") (pintype "passive"))
      (node (ref "JP102") (pin "1") (pinfunction "1_1") (pintype "passive"))
      (node (ref "JP103") (pin "2") (pinfunction "2_2") (pintype "passive"))
      (node (ref "TP24") (pin "TP") (pinfunction "PP_TP") (pintype "input"))
    )
    (net (code "26") (name "Net-(3A-KL)") (class "Default")
      (node (ref "3") (pin "1") (pinfunction "KL_1") (pintype "passive"))
      (node (ref "D16") (pin "2") (pinfunction "-_2") (pintype "passive"))
      (node (ref "R71") (pin "2") (pinfunction "2_2") (pintype "passive"))
      (node (ref "TP14") (pin "TP") (pinfunction "PP_TP") (pintype "input"))
    )
    (net (code "27") (name "Net-(3B-KL)") (class "Default")
      (node (ref "3") (pin "10") (pinfunction "KL_10") (pintype "passive"))
      (node (ref "D3") (pin "2") (pinfunction "-_2") (pintype "passive"))
      (node (ref "D5") (pin "2") (pinfunction "-_2") (pintype "passive"))
      (node (ref "JP5") (pin "1") (pinfunction "1_1") (pintype "passive"))
      (node (ref "SJ1") (pin "1") (pinfunction "1_1") (pintype "passive"))
      (node (ref "TP33") (pin "TP") (pinfunction "PP_TP") (pintype "input"))
    )
    (net (code "28") (name "Net-(3C-KL)") (class "Default")
      (node (ref "3") (pin "11") (pinfunction "KL_11") (pintype "passive"))
      (node (ref "D5") (pin "1") (pinfunction "+_1") (pintype "passive"))
      (node (ref "TP34") (pin "TP") (pinfunction "PP_TP") (pintype "input"))
      (node (ref "X1") (pin "19") (pinfunction "19_19") (pintype "passive"))
    )
    (net (code "29") (name "Net-(3E-KL)") (class "Default")
      (node (ref "3") (pin "2") (pinfunction "KL_2") (pintype "passive"))
      (node (ref "Q6") (pin "2") (pinfunction "C_2") (pintype "passive"))
      (node (ref "TP15") (pin "TP") (pinfunction "PP_TP") (pintype "input"))
    )
    (net (code "30") (name "Net-(3F-KL)") (class "Default")
      (node (ref "3") (pin "3") (pinfunction "KL_3") (pintype "passive"))
      (node (ref "IC5") (pin "11") (pinfunction "O6_11") (pintype "open_collector"))
      (node (ref "TP20") (pin "TP") (pinfunction "PP_TP") (pintype "input"))
    )
    (net (code "31") (name "Net-(3G-KL)") (class "Default")
      (node (ref "3") (pin "4") (pinfunction "KL_4") (pintype "passive"))
      (node (ref "IC5") (pin "10") (pinfunction "O7_10") (pintype "open_collector"))
      (node (ref "TP27") (pin "TP") (pinfunction "PP_TP") (pintype "input"))
    )
    (net (code "32") (name "Net-(3H-KL)") (class "Default")
      (node (ref "3") (pin "5") (pinfunction "KL_5") (pintype "passive"))
      (node (ref "IC5") (pin "12") (pinfunction "O5_12") (pintype "open_collector"))
      (node (ref "TP28") (pin "TP") (pinfunction "PP_TP") (pintype "input"))
    )
    (net (code "33") (name "Net-(3I-KL)") (class "Default")
      (node (ref "3") (pin "6") (pinfunction "KL_6") (pintype "passive"))
      (node (ref "IC5") (pin "13") (pinfunction "O4_13") (pintype "open_collector"))
      (node (ref "TP29") (pin "TP") (pinfunction "PP_TP") (pintype "input"))
    )
    (net (code "34") (name "Net-(3J-KL)") (class "Default")
      (node (ref "3") (pin "7") (pinfunction "KL_7") (pintype "passive"))
      (node (ref "IC5") (pin "14") (pinfunction "O3_14") (pintype "open_collector"))
      (node (ref "TP30") (pin "TP") (pinfunction "PP_TP") (pintype "input"))
    )
    (net (code "35") (name "Net-(3K-KL)") (class "Default")
      (node (ref "3") (pin "8") (pinfunction "KL_8") (pintype "passive"))
      (node (ref "R66") (pin "2") (pinfunction "2_2") (pintype "passive"))
      (node (ref "TP31") (pin "TP") (pinfunction "PP_TP") (pintype "input"))
    )
    (net (code "36") (name "Net-(3L-KL)") (class "Default")
      (node (ref "3") (pin "9") (pinfunction "KL_9") (pintype "passive"))
      (node (ref "D3") (pin "1") (pinfunction "+_1") (pintype "passive"))
      (node (ref "TP32") (pin "TP") (pinfunction "PP_TP") (pintype "input"))
      (node (ref "X1") (pin "17") (pinfunction "17_17") (pintype "passive"))
    )
    (net (code "37") (name "Net-(4B-KL)") (class "Default")
      (node (ref "4") (pin "10") (pinfunction "KL_10") (pintype "passive"))
      (node (ref "TP43") (pin "TP") (pinfunction "PP_TP") (pintype "input"))
      (node (ref "X1") (pin "15") (pinfunction "15_15") (pintype "passive"))
    )
    (net (code "38") (name "Net-(4C-KL)") (class "Default")
      (node (ref "4") (pin "11") (pinfunction "KL_11") (pintype "passive"))
      (node (ref "Q8") (pin "2") (pinfunction "C_2") (pintype "passive"))
      (node (ref "R35") (pin "2") (pinfunction "2_2") (pintype "passive"))
      (node (ref "R51") (pin "1") (pinfunction "1_1") (pintype "passive"))
      (node (ref "TP44") (pin "TP") (pinfunction "PP_TP") (pintype "input"))
    )
    (net (code "39") (name "Net-(4D-KL)") (class "Default")
      (node (ref "4") (pin "12") (pinfunction "KL_12") (pintype "passive"))
      (node (ref "R52") (pin "1") (pinfunction "1_1") (pintype "passive"))
      (node (ref "TP46") (pin "TP") (pinfunction "PP_TP") (pintype "input"))
    )
    (net (code "40") (name "Net-(4E-KL)") (class "Default")
      (node (ref "4") (pin "2") (pinfunction "KL_2") (pintype "passive"))
      (node (ref "D9") (pin "2") (pinfunction "-_2") (pintype "passive"))
      (node (ref "LED1") (pin "K") (pinfunction "C_K") (pintype "passive"))
      (node (ref "TP35") (pin "TP") (pinfunction "PP_TP") (pintype "input"))
      (node (ref "X1") (pin "12") (pinfunction "12_12") (pintype "passive"))
    )
    (net (code "41") (name "Net-(4F-KL)") (class "Default")
      (node (ref "4") (pin "3") (pinfunction "KL_3") (pintype "passive"))
      (node (ref "D8") (pin "2") (pinfunction "-_2") (pintype "passive"))
      (node (ref "LED2") (pin "K") (pinfunction "C_K") (pintype "passive"))
      (node (ref "TP36") (pin "TP") (pinfunction "PP_TP") (pintype "input"))
      (node (ref "X1") (pin "11") (pinfunction "11_11") (pintype "passive"))
    )
    (net (code "42") (name "Net-(4G-KL)") (class "Default")
      (node (ref "4") (pin "4") (pinfunction "KL_4") (pintype "passive"))
      (node (ref "D7") (pin "2") (pinfunction "-_2") (pintype "passive"))
      (node (ref "LED3") (pin "K") (pinfunction "C_K") (pintype "passive"))
      (node (ref "TP37") (pin "TP") (pinfunction "PP_TP") (pintype "input"))
      (node (ref "X1") (pin "10") (pinfunction "10_10") (pintype "passive"))
    )
    (net (code "43") (name "Net-(4H-KL)") (class "Default")
      (node (ref "4") (pin "5") (pinfunction "KL_5") (pintype "passive"))
      (node (ref "D6") (pin "2") (pinfunction "-_2") (pintype "passive"))
      (node (ref "LED4") (pin "K") (pinfunction "C_K") (pintype "passive"))
      (node (ref "TP38") (pin "TP") (pinfunction "PP_TP") (pintype "input"))
      (node (ref "X1") (pin "9") (pinfunction "9_9") (pintype "passive"))
    )
    (net (code "44") (name "Net-(4I-KL)") (class "Default")
      (node (ref "4") (pin "6") (pinfunction "KL_6") (pintype "passive"))
      (node (ref "JP2") (pin "2") (pinfunction "2_2") (pintype "passive"))
      (node (ref "TP39") (pin "TP") (pinfunction "PP_TP") (pintype "input"))
    )
    (net (code "45") (name "Net-(4J-KL)") (class "Default")
      (node (ref "4") (pin "7") (pinfunction "KL_7") (pintype "passive"))
      (node (ref "LED5") (pin "A") (pinfunction "A_A") (pintype "passive"))
      (node (ref "TP40") (pin "TP") (pinfunction "PP_TP") (pintype "input"))
      (node (ref "X1") (pin "8") (pinfunction "8_8") (pintype "passive"))
    )
    (net (code "46") (name "Net-(4K-KL)") (class "Default")
      (node (ref "4") (pin "8") (pinfunction "KL_8") (pintype "passive"))
      (node (ref "D10") (pin "2") (pinfunction "-_2") (pintype "passive"))
      (node (ref "LED6") (pin "K") (pinfunction "C_K") (pintype "passive"))
      (node (ref "TP41") (pin "TP") (pinfunction "PP_TP") (pintype "input"))
      (node (ref "X1") (pin "14") (pinfunction "14_14") (pintype "passive"))
    )
    (net (code "47") (name "Net-(4L-KL)") (class "Default")
      (node (ref "4") (pin "9") (pinfunction "KL_9") (pintype "passive"))
      (node (ref "D7") (pin "1") (pinfunction "+_1") (pintype "passive"))
      (node (ref "D8") (pin "1") (pinfunction "+_1") (pintype "passive"))
      (node (ref "JP3") (pin "1") (pinfunction "1_1") (pintype "passive"))
      (node (ref "JP4") (pin "2") (pinfunction "2_2") (pintype "passive"))
      (node (ref "TP42") (pin "TP") (pinfunction "PP_TP") (pintype "input"))
    )
    (net (code "48") (name "Net-(C3-Pad1)") (class "Default")
      (node (ref "C3") (pin "1") (pinfunction "1_1") (pintype "passive"))
      (node (ref "R25") (pin "1") (pinfunction "1_1") (pintype "passive"))
      (node (ref "R26") (pin "2") (pinfunction "2_2") (pintype "passive"))
    )
    (net (code "49") (name "Net-(C12-Pad1)") (class "Default")
      (node (ref "C12") (pin "1") (pinfunction "1_1") (pintype "passive"))
      (node (ref "R53") (pin "1") (pinfunction "1_1") (pintype "passive"))
      (node (ref "R54") (pin "1") (pinfunction "1_1") (pintype "passive"))
    )
    (net (code "50") (name "Net-(C103-Pad1)") (class "Default")
      (node (ref "C103") (pin "1") (pinfunction "1_1") (pintype "passive"))
      (node (ref "R108") (pin "1") (pinfunction "1_1") (pintype "passive"))
      (node (ref "R112") (pin "1") (pinfunction "1_1") (pintype "passive"))
    )
    (net (code "51") (name "Net-(C107-Pad1)") (class "Default")
      (node (ref "C107") (pin "1") (pinfunction "1_1") (pintype "passive"))
      (node (ref "R125") (pin "1") (pinfunction "1_1") (pintype "passive"))
      (node (ref "R130") (pin "2") (pinfunction "2_2") (pintype "passive"))
    )
    (net (code "52") (name "Net-(D1--)") (class "Default")
      (node (ref "D1") (pin "2") (pinfunction "-_2") (pintype "passive"))
      (node (ref "R7") (pin "1") (pinfunction "1_1") (pintype "passive"))
    )
    (net (code "53") (name "Net-(D2-+)") (class "Default")
      (node (ref "D2") (pin "1") (pinfunction "+_1") (pintype "passive"))
      (node (ref "R13") (pin "1") (pinfunction "1_1") (pintype "passive"))
      (node (ref "X101") (pin "1") (pinfunction "1_1") (pintype "passive"))
    )
    (net (code "54") (name "Net-(D6-+)") (class "Default")
      (node (ref "D6") (pin "1") (pinfunction "+_1") (pintype "passive"))
      (node (ref "R15") (pin "1") (pinfunction "1_1") (pintype "passive"))
    )
    (net (code "55") (name "Net-(D9-+)") (class "Default")
      (node (ref "D9") (pin "1") (pinfunction "+_1") (pintype "passive"))
      (node (ref "JP3") (pin "2") (pinfunction "2_2") (pintype "passive"))
    )
    (net (code "56") (name "Net-(D10-+)") (class "Default")
      (node (ref "D10") (pin "1") (pinfunction "+_1") (pintype "passive"))
      (node (ref "JP4") (pin "1") (pinfunction "1_1") (pintype "passive"))
    )
    (net (code "57") (name "Net-(D11--)") (class "Default")
      (node (ref "D11") (pin "2") (pinfunction "-_2") (pintype "passive"))
      (node (ref "Q4") (pin "2") (pinfunction "C_2") (pintype "passive"))
      (node (ref "START1") (pin "TP") (pinfunction "PP_TP") (pintype "input"))
      (node (ref "X1") (pin "5") (pinfunction "5_5") (pintype "passive"))
    )
    (net (code "58") (name "Net-(D12-+)") (class "Default")
      (node (ref "D12") (pin "1") (pinfunction "+_1") (pintype "passive"))
      (node (ref "R47") (pin "1") (pinfunction "1_1") (pintype "passive"))
    )
    (net (code "59") (name "Net-(D12--)") (class "Default")
      (node (ref "C9") (pin "2") (pinfunction "2_2") (pintype "passive"))
      (node (ref "D12") (pin "2") (pinfunction "-_2") (pintype "passive"))
      (node (ref "D17") (pin "1") (pinfunction "C_1") (pintype "passive"))
      (node (ref "IC8") (pin "2") (pinfunction "TR_2") (pintype "input"))
      (node (ref "IC8") (pin "6") (pinfunction "THR_6") (pintype "input"))
      (node (ref "R45") (pin "1") (pinfunction "1_1") (pintype "passive"))
    )
    (net (code "60") (name "Net-(D14-PadC)") (class "Default")
      (node (ref "D14") (pin "C") (pinfunction "C_C") (pintype "passive"))
      (node (ref "R21") (pin "2") (pinfunction "2_2") (pintype "passive"))
      (node (ref "X1") (pin "22") (pinfunction "22_22") (pintype "passive"))
    )
    (net (code "61") (name "Net-(D15--)") (class "Default")
      (node (ref "D15") (pin "2") (pinfunction "-_2") (pintype "passive"))
      (node (ref "R64") (pin "1") (pinfunction "1_1") (pintype "passive"))
    )
    (net (code "62") (name "Net-(D16-+)") (class "Default")
      (node (ref "D16") (pin "1") (pinfunction "+_1") (pintype "passive"))
      (node (ref "R71") (pin "1") (pinfunction "1_1") (pintype "passive"))
      (node (ref "X1") (pin "1") (pinfunction "1_1") (pintype "passive"))
    )
    (net (code "63") (name "Net-(D104-PadC)") (class "Default")
      (node (ref "D104") (pin "C") (pinfunction "C_C") (pintype "passive"))
      (node (ref "R105") (pin "2") (pinfunction "2_2") (pintype "passive"))
      (node (ref "X101") (pin "22") (pinfunction "22_22") (pintype "passive"))
    )
    (net (code "64") (name "Net-(D105--)") (class "Default")
      (node (ref "D105") (pin "2") (pinfunction "-_2") (pintype "passive"))
      (node (ref "Q104") (pin "2") (pinfunction "C_2") (pintype "passive"))
      (node (ref "START") (pin "TP") (pinfunction "PP_TP") (pintype "input"))
      (node (ref "X101") (pin "5") (pinfunction "5_5") (pintype "passive"))
    )
    (net (code "65") (name "Net-(D106-+)") (class "Default")
      (node (ref "D106") (pin "1") (pinfunction "+_1") (pintype "passive"))
      (node (ref "R127") (pin "1") (pinfunction "1_1") (pintype "passive"))
    )
    (net (code "66") (name "Net-(D109-+)") (class "Default")
      (node (ref "D109") (pin "1") (pinfunction "+_1") (pintype "passive"))
      (node (ref "JP102") (pin "2") (pinfunction "2_2") (pintype "passive"))
    )
    (net (code "67") (name "Net-(D110-+)") (class "Default")
      (node (ref "D110") (pin "1") (pinfunction "+_1") (pintype "passive"))
      (node (ref "JP103") (pin "1") (pinfunction "1_1") (pintype "passive"))
    )
    (net (code "68") (name "Net-(D112-+)") (class "Default")
      (node (ref "D112") (pin "1") (pinfunction "+_1") (pintype "passive"))
      (node (ref "R140") (pin "1") (pinfunction "1_1") (pintype "passive"))
    )
    (net (code "69") (name "Net-(D112--)") (class "Default")
      (node (ref "C109") (pin "2") (pinfunction "2_2") (pintype "passive"))
      (node (ref "D112") (pin "2") (pinfunction "-_2") (pintype "passive"))
      (node (ref "D4") (pin "1") (pinfunction "C_1") (pintype "passive"))
      (node (ref "IC110") (pin "2") (pinfunction "TR_2") (pintype "input"))
      (node (ref "IC110") (pin "6") (pinfunction "THR_6") (pintype "input"))
      (node (ref "R141") (pin "1") (pinfunction "1_1") (pintype "passive"))
    )
    (net (code "70") (name "Net-(IC1-+IN)") (class "Default")
      (node (ref "C2") (pin "2") (pinfunction "2_2") (pintype "passive"))
      (node (ref "IC1") (pin "2") (pinfunction "+IN_2") (pintype "input"))
      (node (ref "R10") (pin "2") (pinfunction "2_2") (pintype "passive"))
      (node (ref "R11") (pin "2") (pinfunction "2_2") (pintype "passive"))
    )
    (net (code "71") (name "Net-(IC1--IN)") (class "Default")
      (node (ref "IC1") (pin "3") (pinfunction "-IN_3") (pintype "input"))
      (node (ref "PAD2") (pin "1") (pinfunction "P_1") (pintype "passive"))
      (node (ref "R12") (pin "2") (pinfunction "2_2") (pintype "passive"))
      (node (ref "R14") (pin "1") (pinfunction "1_1") (pintype "passive"))
    )
    (net (code "72") (name "Net-(IC1-OUT)") (class "Default")
      (node (ref "IC1") (pin "7") (pinfunction "OUT_7") (pintype "output"))
      (node (ref "Q3") (pin "3") (pinfunction "D_3") (pintype "passive"))
      (node (ref "R10") (pin "1") (pinfunction "1_1") (pintype "passive"))
      (node (ref "R8") (pin "2") (pinfunction "2_2") (pintype "passive"))
    )
    (net (code "73") (name "Net-(IC2A-A)") (class "Default")
      (node (ref "IC2") (pin "10") (pinfunction "A_10") (pintype "input"))
      (node (ref "R20") (pin "1") (pinfunction "1_1") (pintype "passive"))
      (node (ref "R61") (pin "1") (pinfunction "1_1") (pintype "passive"))
      (node (ref "R61") (pin "2") (pinfunction "2_2") (pintype "passive"))
      (node (ref "X1") (pin "4") (pinfunction "4_4") (pintype "passive"))
      (node (ref "X2") (pin "2") (pinfunction "S_2") (pintype "passive"))
    )
    (net (code "74") (name "Net-(IC2A-B)") (class "Default")
      (node (ref "IC2") (pin "13") (pinfunction "B_13") (pintype "input"))
      (node (ref "R19") (pin "1") (pinfunction "1_1") (pintype "passive"))
      (node (ref "R60") (pin "1") (pinfunction "1_1") (pintype "passive"))
      (node (ref "R60") (pin "2") (pinfunction "2_2") (pintype "passive"))
      (node (ref "X1") (pin "3") (pinfunction "3_3") (pintype "passive"))
      (node (ref "X2") (pin "3") (pinfunction "S_3") (pintype "passive"))
    )
    (net (code "75") (name "Net-(IC2A-C)") (class "Default")
      (node (ref "IC2") (pin "12") (pinfunction "C_12") (pintype "input"))
      (node (ref "R18") (pin "1") (pinfunction "1_1") (pintype "passive"))
      (node (ref "R59") (pin "1") (pinfunction "1_1") (pintype "passive"))
      (node (ref "R59") (pin "2") (pinfunction "2_2") (pintype "passive"))
      (node (ref "X1") (pin "2") (pinfunction "2_2") (pintype "passive"))
      (node (ref "X2") (pin "4") (pinfunction "S_4") (pintype "passive"))
    )
    (net (code "76") (name "Net-(IC2A-Q0)") (class "Default")
      (node (ref "IC2") (pin "3") (pinfunction "Q0_3") (pintype "output"))
      (node (ref "IC5") (pin "1") (pinfunction "I1_1") (pintype "input"))
      (node (ref "IC5") (pin "2") (pinfunction "I2_2") (pintype "input"))
      (node (ref "Q10") (pin "1") (pinfunction "G_1") (pintype "passive"))
      (node (ref "Q11") (pin "1") (pinfunction "G_1") (pintype "passive"))
    )
    (net (code "77") (name "Net-(IC2A-Q1)") (class "Default")
      (node (ref "IC2") (pin "14") (pinfunction "Q1_14") (pintype "output"))
      (node (ref "IC5") (pin "6") (pinfunction "I6_6") (pintype "input"))
    )
    (net (code "78") (name "Net-(IC2A-Q2)") (class "Default")
      (node (ref "IC2") (pin "2") (pinfunction "Q2_2") (pintype "output"))
      (node (ref "IC5") (pin "7") (pinfunction "I7_7") (pintype "input"))
    )
    (net (code "79") (name "Net-(IC2A-Q3)") (class "Default")
      (node (ref "IC2") (pin "15") (pinfunction "Q3_15") (pintype "output"))
      (node (ref "IC5") (pin "5") (pinfunction "I5_5") (pintype "input"))
    )
    (net (code "80") (name "Net-(IC2A-Q4)") (class "Default")
      (node (ref "IC2") (pin "1") (pinfunction "Q4_1") (pintype "output"))
      (node (ref "IC5") (pin "4") (pinfunction "I4_4") (pintype "input"))
    )
    (net (code "81") (name "Net-(IC2A-Q5)") (class "Default")
      (node (ref "IC2") (pin "6") (pinfunction "Q5_6") (pintype "output"))
      (node (ref "IC5") (pin "3") (pinfunction "I3_3") (pintype "input"))
    )
    (net (code "82") (name "Net-(IC4-ADJ)") (class "Default")
      (node (ref "IC4") (pin "1") (pinfunction "ADJ_1") (pintype "input"))
      (node (ref "R16") (pin "1") (pinfunction "1_1") (pintype "passive"))
      (node (ref "R23") (pin "2") (pinfunction "2_2") (pintype "passive"))
      (node (ref "X1") (pin "7") (pinfunction "7_7") (pintype "passive"))
    )
    (net (code "83") (name "Net-(IC4-VI)") (class "Default")
      (node (ref "IC4") (pin "3") (pinfunction "VI_3") (pintype "input"))
      (node (ref "Q7") (pin "2") (pinfunction "C_2") (pintype "passive"))
    )
    (net (code "84") (name "Net-(IC4-VO)") (class "Default")
      (node (ref "IC4") (pin "2") (pinfunction "VO_2") (pintype "passive"))
      (node (ref "R16") (pin "2") (pinfunction "2_2") (pintype "passive"))
    )
    (net (code "85") (name "Net-(IC5-O1)") (class "Default")
      (node (ref "IC5") (pin "16") (pinfunction "O1_16") (pintype "open_collector"))
      (node (ref "Q10") (pin "3") (pinfunction "D_3") (pintype "passive"))
      (node (ref "R66") (pin "1") (pinfunction "1_1") (pintype "passive"))
    )
    (net (code "86") (name "Net-(IC5-O2)") (class "Default")
      (node (ref "IC5") (pin "15") (pinfunction "O2_15") (pintype "open_collector"))
      (node (ref "R38") (pin "1") (pinfunction "1_1") (pintype "passive"))
    )
    (net (code "87") (name "Net-(IC6A-+IN)") (class "Default")
      (node (ref "IC6") (pin "11") (pinfunction "+IN_11") (pintype "input"))
      (node (ref "IC6") (pin "5") (pinfunction "+IN_5") (pintype "input"))
      (node (ref "R27") (pin "1") (pinfunction "1_1") (pintype "passive"))
      (node (ref "R28") (pin "2") (pinfunction "2_2") (pintype "passive"))
      (node (ref "R29") (pin "2") (pinfunction "2_2") (pintype "passive"))
    )
    (net (code "88") (name "Net-(IC6A--IN)") (class "Default")
      (node (ref "C4") (pin "1") (pinfunction "1_1") (pintype "passive"))
      (node (ref "IC6") (pin "10") (pinfunction "-IN_10") (pintype "input"))
      (node (ref "IC6") (pin "4") (pinfunction "-IN_4") (pintype "input"))
      (node (ref "R26") (pin "1") (pinfunction "1_1") (pintype "passive"))
    )
    (net (code "89") (name "Net-(IC6A-OUT)") (class "Default")
      (node (ref "IC6") (pin "2") (pinfunction "OUT_2") (pintype "open_collector"))
      (node (ref "R29") (pin "1") (pinfunction "1_1") (pintype "passive"))
    )
    (net (code "90") (name "Net-(IC6B-+IN)") (class "Default")
      (node (ref "IC6") (pin "7") (pinfunction "+IN_7") (pintype "input"))
      (node (ref "R24") (pin "1") (pinfunction "1_1") (pintype "passive"))
      (node (ref "R41") (pin "1") (pinfunction "1_1") (pintype "passive"))
    )
    (net (code "91") (name "Net-(IC6B--IN)") (class "Default")
      (node (ref "IC6") (pin "6") (pinfunction "-IN_6") (pintype "input"))
      (node (ref "IC6") (pin "8") (pinfunction "-IN_8") (pintype "input"))
      (node (ref "R23") (pin "1") (pinfunction "1_1") (pintype "passive"))
    )
    (net (code "92") (name "Net-(IC6B-OUT)") (class "Default")
      (node (ref "IC6") (pin "1") (pinfunction "OUT_1") (pintype "open_collector"))
      (node (ref "R25") (pin "2") (pinfunction "2_2") (pintype "passive"))
      (node (ref "R30") (pin "2") (pinfunction "2_2") (pintype "passive"))
    )
    (net (code "93") (name "Net-(IC6C-+IN)") (class "Default")
      (node (ref "C7") (pin "1") (pinfunction "1_1") (pintype "passive"))
      (node (ref "IC6") (pin "9") (pinfunction "+IN_9") (pintype "input"))
      (node (ref "R32") (pin "2") (pinfunction "2_2") (pintype "passive"))
      (node (ref "R41") (pin "2") (pinfunction "2_2") (pintype "passive"))
    )
    (net (code "94") (name "Net-(IC6C-OUT)") (class "Default")
      (node (ref "C8") (pin "2") (pinfunction "2_2") (pintype "passive"))
      (node (ref "IC6") (pin "14") (pinfunction "OUT_14") (pintype "open_collector"))
      (node (ref "R31") (pin "2") (pinfunction "2_2") (pintype "passive"))
    )
    (net (code "95") (name "Net-(IC6D-OUT)") (class "Default")
      (node (ref "IC6") (pin "13") (pinfunction "OUT_13") (pintype "open_collector"))
      (node (ref "JP2") (pin "1") (pinfunction "1_1") (pintype "passive"))
      (node (ref "Q9") (pin "1") (pinfunction "G_1") (pintype "passive"))
      (node (ref "R44") (pin "2") (pinfunction "2_2") (pintype "passive"))
    )
    (net (code "96") (name "Net-(IC8-CV)") (class "Default")
      (node (ref "IC8") (pin "5") (pinfunction "CV_5") (pintype "input"))
      (node (ref "R46") (pin "2") (pinfunction "2_2") (pintype "passive"))
    )
    (net (code "97") (name "Net-(IC8-Q)") (class "Default")
      (node (ref "IC8") (pin "3") (pinfunction "Q_3") (pintype "output"))
      (node (ref "IC9") (pin "12") (pinfunction "A_12") (pintype "input"))
      (node (ref "R46") (pin "1") (pinfunction "1_1") (pintype "passive"))
    )
    (net (code "98") (name "Net-(IC9B-B)") (class "Default")
      (node (ref "IC9") (pin "11") (pinfunction "B_11") (pintype "input"))
      (node (ref "IC9") (pin "9") (pinfunction "~{Q}_9") (pintype "output"))
      (node (ref "R52") (pin "2") (pinfunction "2_2") (pintype "passive"))
    )
    (net (code "99") (name "Net-(IC9B-Q)") (class "Default")
      (node (ref "IC9") (pin "10") (pinfunction "Q_10") (pintype "output"))
      (node (ref "PAD4") (pin "1") (pinfunction "P_1") (pintype "passive"))
    )
    (net (code "100") (name "Net-(IC9B-T2)") (class "Default")
      (node (ref "C11") (pin "1") (pinfunction "1_1") (pintype "passive"))
      (node (ref "IC9") (pin "14") (pinfunction "T2_14") (pintype "input"))
      (node (ref "R50") (pin "1") (pinfunction "1_1") (pintype "passive"))
    )
    (net (code "101") (name "Net-(IC11A-+IN)") (class "Default")
      (node (ref "C6") (pin "1") (pinfunction "1_1") (pintype "passive"))
      (node (ref "IC11") (pin "3") (pinfunction "+IN_3") (pintype "input"))
      (node (ref "R21") (pin "1") (pinfunction "1_1") (pintype "passive"))
    )
    (net (code "102") (name "Net-(IC11A--IN)") (class "Default")
      (node (ref "IC11") (pin "2") (pinfunction "-IN_2") (pintype "input"))
      (node (ref "R22") (pin "2") (pinfunction "2_2") (pintype "passive"))
    )
    (net (code "103") (name "Net-(IC11A-OUT)") (class "Default")
      (node (ref "IC11") (pin "1") (pinfunction "OUT_1") (pintype "output"))
      (node (ref "R53") (pin "2") (pinfunction "2_2") (pintype "passive"))
    )
    (net (code "104") (name "Net-(IC11B-+IN)") (class "Default")
      (node (ref "IC11") (pin "5") (pinfunction "+IN_5") (pintype "input"))
      (node (ref "Q11") (pin "3") (pinfunction "D_3") (pintype "passive"))
      (node (ref "R54") (pin "2") (pinfunction "2_2") (pintype "passive"))
      (node (ref "R55") (pin "2") (pinfunction "2_2") (pintype "passive"))
    )
    (net (code "105") (name "Net-(IC11B--IN)") (class "Default")
      (node (ref "IC11") (pin "6") (pinfunction "-IN_6") (pintype "input"))
      (node (ref "R56") (pin "1") (pinfunction "1_1") (pintype "passive"))
      (node (ref "R57") (pin "2") (pinfunction "2_2") (pintype "passive"))
    )
    (net (code "106") (name "Net-(IC11B-OUT)") (class "Default")
      (node (ref "IC11") (pin "7") (pinfunction "OUT_7") (pintype "output"))
      (node (ref "R42") (pin "1") (pinfunction "1_1") (pintype "passive"))
      (node (ref "R55") (pin "1") (pinfunction "1_1") (pintype "passive"))
    )
    (net (code "107") (name "Net-(IC12-+IN)") (class "Default")
      (node (ref "C14") (pin "2") (pinfunction "2_2") (pintype "passive"))
      (node (ref "IC12") (pin "2") (pinfunction "+IN_2") (pintype "input"))
      (node (ref "R68") (pin "2") (pinfunction "2_2") (pintype "passive"))
      (node (ref "R69") (pin "2") (pinfunction "2_2") (pintype "passive"))
    )
    (net (code "108") (name "Net-(IC12--IN)") (class "Default")
      (node (ref "IC12") (pin "3") (pinfunction "-IN_3") (pintype "input"))
      (node (ref "PAD5") (pin "1") (pinfunction "P_1") (pintype "passive"))
      (node (ref "R70") (pin "2") (pinfunction "2_2") (pintype "passive"))
      (node (ref "R72") (pin "1") (pinfunction "1_1") (pintype "passive"))
    )
    (net (code "109") (name "Net-(IC12-OUT)") (class "Default")
      (node (ref "IC12") (pin "7") (pinfunction "OUT_7") (pintype "output"))
      (node (ref "Q13") (pin "3") (pinfunction "D_3") (pintype "passive"))
      (node (ref "R67") (pin "2") (pinfunction "2_2") (pintype "passive"))
      (node (ref "R68") (pin "1") (pinfunction "1_1") (pintype "passive"))
    )
    (net (code "110") (name "Net-(IC101A-+IN)") (class "Default")
      (node (ref "C101") (pin "1") (pinfunction "1_1") (pintype "passive"))
      (node (ref "IC101") (pin "3") (pinfunction "+IN_3") (pintype "input"))
      (node (ref "R105") (pin "1") (pinfunction "1_1") (pintype "passive"))
    )
    (net (code "111") (name "Net-(IC101A--IN)") (class "Default")
      (node (ref "IC101") (pin "2") (pinfunction "-IN_2") (pintype "input"))
      (node (ref "R107") (pin "2") (pinfunction "2_2") (pintype "passive"))
    )
    (net (code "112") (name "Net-(IC101A-OUT)") (class "Default")
      (node (ref "IC101") (pin "1") (pinfunction "OUT_1") (pintype "output"))
      (node (ref "R108") (pin "2") (pinfunction "2_2") (pintype "passive"))
    )
    (net (code "113") (name "Net-(IC101B-+IN)") (class "Default")
      (node (ref "IC101") (pin "5") (pinfunction "+IN_5") (pintype "input"))
      (node (ref "Q1") (pin "3") (pinfunction "D_3") (pintype "passive"))
      (node (ref "R112") (pin "2") (pinfunction "2_2") (pintype "passive"))
      (node (ref "R117") (pin "2") (pinfunction "2_2") (pintype "passive"))
    )
    (net (code "114") (name "Net-(IC101B--IN)") (class "Default")
      (node (ref "IC101") (pin "6") (pinfunction "-IN_6") (pintype "input"))
      (node (ref "R113") (pin "1") (pinfunction "1_1") (pintype "passive"))
      (node (ref "R114") (pin "2") (pinfunction "2_2") (pintype "passive"))
    )
    (net (code "115") (name "Net-(IC101B-OUT)") (class "Default")
      (node (ref "IC101") (pin "7") (pinfunction "OUT_7") (pintype "output"))
      (node (ref "R116") (pin "1") (pinfunction "1_1") (pintype "passive"))
      (node (ref "R117") (pin "1") (pinfunction "1_1") (pintype "passive"))
    )
    (net (code "116") (name "Net-(IC105A-A)") (class "Default")
      (node (ref "IC105") (pin "10") (pinfunction "A_10") (pintype "input"))
      (node (ref "R111") (pin "1") (pinfunction "1_1") (pintype "passive"))
      (node (ref "R3") (pin "1") (pinfunction "1_1") (pintype "passive"))
      (node (ref "R3") (pin "2") (pinfunction "2_2") (pintype "passive"))
      (node (ref "X101") (pin "4") (pinfunction "4_4") (pintype "passive"))
      (node (ref "X103") (pin "2") (pinfunction "S_2") (pintype "passive"))
    )
    (net (code "117") (name "Net-(IC105A-B)") (class "Default")
      (node (ref "IC105") (pin "13") (pinfunction "B_13") (pintype "input"))
      (node (ref "R110") (pin "1") (pinfunction "1_1") (pintype "passive"))
      (node (ref "R2") (pin "1") (pinfunction "1_1") (pintype "passive"))
      (node (ref "R2") (pin "2") (pinfunction "2_2") (pintype "passive"))
      (node (ref "X101") (pin "3") (pinfunction "3_3") (pintype "passive"))
      (node (ref "X103") (pin "3") (pinfunction "S_3") (pintype "passive"))
    )
    (net (code "118") (name "Net-(IC105A-C)") (class "Default")
      (node (ref "IC105") (pin "12") (pinfunction "C_12") (pintype "input"))
      (node (ref "R1") (pin "1") (pinfunction "1_1") (pintype "passive"))
      (node (ref "R1") (pin "2") (pinfunction "2_2") (pintype "passive"))
      (node (ref "R109") (pin "1") (pinfunction "1_1") (pintype "passive"))
      (node (ref "X101") (pin "2") (pinfunction "2_2") (pintype "passive"))
      (node (ref "X103") (pin "4") (pinfunction "S_4") (pintype "passive"))
    )
    (net (code "119") (name "Net-(IC105A-Q0)") (class "Default")
      (node (ref "IC105") (pin "3") (pinfunction "Q0_3") (pintype "output"))
      (node (ref "IC107") (pin "1") (pinfunction "I1_1") (pintype "input"))
      (node (ref "IC107") (pin "2") (pinfunction "I2_2") (pintype "input"))
      (node (ref "Q1") (pin "1") (pinfunction "G_1") (pintype "passive"))
      (node (ref "Q106") (pin "1") (pinfunction "G_1") (pintype "passive"))
    )
    (net (code "120") (name "Net-(IC105A-Q1)") (class "Default")
      (node (ref "IC105") (pin "14") (pinfunction "Q1_14") (pintype "output"))
      (node (ref "IC107") (pin "6") (pinfunction "I6_6") (pintype "input"))
    )
    (net (code "121") (name "Net-(IC105A-Q2)") (class "Default")
      (node (ref "IC105") (pin "2") (pinfunction "Q2_2") (pintype "output"))
      (node (ref "IC107") (pin "7") (pinfunction "I7_7") (pintype "input"))
    )
    (net (code "122") (name "Net-(IC105A-Q3)") (class "Default")
      (node (ref "IC105") (pin "15") (pinfunction "Q3_15") (pintype "output"))
      (node (ref "IC107") (pin "5") (pinfunction "I5_5") (pintype "input"))
    )
    (net (code "123") (name "Net-(IC105A-Q4)") (class "Default")
      (node (ref "IC105") (pin "1") (pinfunction "Q4_1") (pintype "output"))
      (node (ref "IC107") (pin "4") (pinfunction "I4_4") (pintype "input"))
    )
    (net (code "124") (name "Net-(IC105A-Q5)") (class "Default")
      (node (ref "IC105") (pin "6") (pinfunction "Q5_6") (pintype "output"))
      (node (ref "IC107") (pin "3") (pinfunction "I3_3") (pintype "input"))
    )
    (net (code "125") (name "Net-(IC107-O1)") (class "Default")
      (node (ref "IC107") (pin "16") (pinfunction "O1_16") (pintype "open_collector"))
      (node (ref "Q106") (pin "3") (pinfunction "D_3") (pintype "passive"))
      (node (ref "R9") (pin "1") (pinfunction "1_1") (pintype "passive"))
    )
    (net (code "126") (name "Net-(IC107-O2)") (class "Default")
      (node (ref "IC107") (pin "15") (pinfunction "O2_15") (pintype "open_collector"))
      (node (ref "R128") (pin "1") (pinfunction "1_1") (pintype "passive"))
    )
    (net (code "127") (name "Net-(IC108A-+IN)") (class "Default")
      (node (ref "IC108") (pin "11") (pinfunction "+IN_11") (pintype "input"))
      (node (ref "IC108") (pin "5") (pinfunction "+IN_5") (pintype "input"))
      (node (ref "R131") (pin "1") (pinfunction "1_1") (pintype "passive"))
      (node (ref "R132") (pin "2") (pinfunction "2_2") (pintype "passive"))
      (node (ref "R133") (pin "2") (pinfunction "2_2") (pintype "passive"))
    )
    (net (code "128") (name "Net-(IC108A--IN)") (class "Default")
      (node (ref "C108") (pin "1") (pinfunction "1_1") (pintype "passive"))
      (node (ref "IC108") (pin "10") (pinfunction "-IN_10") (pintype "input"))
      (node (ref "IC108") (pin "4") (pinfunction "-IN_4") (pintype "input"))
      (node (ref "R130") (pin "1") (pinfunction "1_1") (pintype "passive"))
    )
    (net (code "129") (name "Net-(IC108A-OUT)") (class "Default")
      (node (ref "IC108") (pin "2") (pinfunction "OUT_2") (pintype "open_collector"))
      (node (ref "R133") (pin "1") (pinfunction "1_1") (pintype "passive"))
    )
    (net (code "130") (name "Net-(IC108B-+IN)") (class "Default")
      (node (ref "IC108") (pin "7") (pinfunction "+IN_7") (pintype "input"))
      (node (ref "R121") (pin "1") (pinfunction "1_1") (pintype "passive"))
      (node (ref "R122") (pin "1") (pinfunction "1_1") (pintype "passive"))
    )
    (net (code "131") (name "Net-(IC108B--IN)") (class "Default")
      (node (ref "IC108") (pin "6") (pinfunction "-IN_6") (pintype "input"))
      (node (ref "IC108") (pin "8") (pinfunction "-IN_8") (pintype "input"))
      (node (ref "R120") (pin "1") (pinfunction "1_1") (pintype "passive"))
    )
    (net (code "132") (name "Net-(IC108B-OUT)") (class "Default")
      (node (ref "IC108") (pin "1") (pinfunction "OUT_1") (pintype "open_collector"))
      (node (ref "R124") (pin "2") (pinfunction "2_2") (pintype "passive"))
      (node (ref "R125") (pin "2") (pinfunction "2_2") (pintype "passive"))
    )
    (net (code "133") (name "Net-(IC108C-+IN)") (class "Default")
      (node (ref "C105") (pin "1") (pinfunction "1_1") (pintype "passive"))
      (node (ref "IC108") (pin "9") (pinfunction "+IN_9") (pintype "input"))
      (node (ref "R122") (pin "2") (pinfunction "2_2") (pintype "passive"))
      (node (ref "R123") (pin "2") (pinfunction "2_2") (pintype "passive"))
    )
    (net (code "134") (name "Net-(IC108C-OUT)") (class "Default")
      (node (ref "C106") (pin "2") (pinfunction "2_2") (pintype "passive"))
      (node (ref "IC108") (pin "14") (pinfunction "OUT_14") (pintype "open_collector"))
      (node (ref "R126") (pin "2") (pinfunction "2_2") (pintype "passive"))
    )
    (net (code "135") (name "Net-(IC108D-OUT)") (class "Default")
      (node (ref "IC108") (pin "13") (pinfunction "OUT_13") (pintype "open_collector"))
      (node (ref "JP105") (pin "1") (pinfunction "1_1") (pintype "passive"))
      (node (ref "Q107") (pin "1") (pinfunction "G_1") (pintype "passive"))
      (node (ref "R135") (pin "2") (pinfunction "2_2") (pintype "passive"))
    )
    (net (code "136") (name "Net-(IC109-ADJ)") (class "Default")
      (node (ref "IC109") (pin "1") (pinfunction "ADJ_1") (pintype "input"))
      (node (ref "R120") (pin "2") (pinfunction "2_2") (pintype "passive"))
      (node (ref "R134") (pin "1") (pinfunction "1_1") (pintype "passive"))
      (node (ref "X101") (pin "7") (pinfunction "7_7") (pintype "passive"))
    )
    (net (code "137") (name "Net-(IC109-VI)") (class "Default")
      (node (ref "IC109") (pin "3") (pinfunction "VI_3") (pintype "input"))
      (node (ref "Q105") (pin "2") (pinfunction "C_2") (pintype "passive"))
    )
    (net (code "138") (name "Net-(IC109-VO)") (class "Default")
      (node (ref "IC109") (pin "2") (pinfunction "VO_2") (pintype "passive"))
      (node (ref "R134") (pin "2") (pinfunction "2_2") (pintype "passive"))
    )
    (net (code "139") (name "Net-(IC110-CV)") (class "Default")
      (node (ref "IC110") (pin "5") (pinfunction "CV_5") (pintype "input"))
      (node (ref "R144") (pin "2") (pinfunction "2_2") (pintype "passive"))
    )
    (net (code "140") (name "Net-(IC110-Q)") (class "Default")
      (node (ref "IC110") (pin "3") (pinfunction "Q_3") (pintype "output"))
      (node (ref "IC111") (pin "12") (pinfunction "A_12") (pintype "input"))
      (node (ref "R144") (pin "1") (pinfunction "1_1") (pintype "passive"))
    )
    (net (code "141") (name "Net-(IC111B-B)") (class "Default")
      (node (ref "IC111") (pin "11") (pinfunction "B_11") (pintype "input"))
      (node (ref "IC111") (pin "9") (pinfunction "~{Q}_9") (pintype "output"))
      (node (ref "R146") (pin "2") (pinfunction "2_2") (pintype "passive"))
    )
    (net (code "142") (name "Net-(IC111B-Q)") (class "Default")
      (node (ref "IC111") (pin "10") (pinfunction "Q_10") (pintype "output"))
      (node (ref "PAD1") (pin "1") (pinfunction "P_1") (pintype "passive"))
    )
    (net (code "143") (name "Net-(IC111B-T2)") (class "Default")
      (node (ref "C110") (pin "1") (pinfunction "1_1") (pintype "passive"))
      (node (ref "IC111") (pin "14") (pinfunction "T2_14") (pintype "input"))
      (node (ref "R145") (pin "1") (pinfunction "1_1") (pintype "passive"))
    )
    (net (code "144") (name "Net-(JP1-Pad1)") (class "Default")
      (node (ref "JP1") (pin "1") (pinfunction "1_1") (pintype "passive"))
      (node (ref "R51") (pin "2") (pinfunction "2_2") (pintype "passive"))
    )
    (net (code "145") (name "Net-(JP2-Pad3)") (class "Default")
      (node (ref "JP2") (pin "3") (pinfunction "3_3") (pintype "passive"))
      (node (ref "R43") (pin "1") (pinfunction "1_1") (pintype "passive"))
    )
    (net (code "146") (name "Net-(JP5-Pad2)") (class "Default")
      (node (ref "JP5") (pin "2") (pinfunction "2_2") (pintype "passive"))
      (node (ref "R48") (pin "2") (pinfunction "2_2") (pintype "passive"))
      (node (ref "R49") (pin "2") (pinfunction "2_2") (pintype "passive"))
      (node (ref "SJ1") (pin "2") (pinfunction "2_2") (pintype "passive"))
    )
    (net (code "147") (name "Net-(JP101-Pad1)") (class "Default")
      (node (ref "JP101") (pin "1") (pinfunction "1_1") (pintype "passive"))
      (node (ref "R119") (pin "2") (pinfunction "2_2") (pintype "passive"))
    )
    (net (code "148") (name "Net-(JP104-Pad2)") (class "Default")
      (node (ref "JP104") (pin "2") (pinfunction "2_2") (pintype "passive"))
      (node (ref "R136") (pin "2") (pinfunction "2_2") (pintype "passive"))
      (node (ref "R137") (pin "2") (pinfunction "2_2") (pintype "passive"))
      (node (ref "SJ101") (pin "2") (pinfunction "2_2") (pintype "passive"))
    )
    (net (code "149") (name "Net-(JP105-Pad3)") (class "Default")
      (node (ref "JP105") (pin "3") (pinfunction "3_3") (pintype "passive"))
      (node (ref "R138") (pin "1") (pinfunction "1_1") (pintype "passive"))
    )
    (net (code "150") (name "Net-(LED1-PadA)") (class "Default")
      (node (ref "LED1") (pin "A") (pinfunction "A_A") (pintype "passive"))
      (node (ref "LED2") (pin "A") (pinfunction "A_A") (pintype "passive"))
      (node (ref "LED3") (pin "A") (pinfunction "A_A") (pintype "passive"))
      (node (ref "LED4") (pin "A") (pinfunction "A_A") (pintype "passive"))
      (node (ref "LED6") (pin "A") (pinfunction "A_A") (pintype "passive"))
      (node (ref "R37") (pin "1") (pinfunction "1_1") (pintype "passive"))
    )
    (net (code "151") (name "Net-(LED5-C)") (class "Default")
      (node (ref "LED5") (pin "K") (pinfunction "C_K") (pintype "passive"))
      (node (ref "R36") (pin "1") (pinfunction "1_1") (pintype "passive"))
    )
    (net (code "152") (name "Net-(LED101-C)") (class "Default")
      (node (ref "LED101") (pin "K") (pinfunction "C_K") (pintype "passive"))
      (node (ref "R143") (pin "1") (pinfunction "1_1") (pintype "passive"))
    )
    (net (code "153") (name "Net-(LED102-PadA)") (class "Default")
      (node (ref "LED102") (pin "A") (pinfunction "A_A") (pintype "passive"))
      (node (ref "LED103") (pin "A") (pinfunction "A_A") (pintype "passive"))
      (node (ref "LED104") (pin "A") (pinfunction "A_A") (pintype "passive"))
      (node (ref "LED105") (pin "A") (pinfunction "A_A") (pintype "passive"))
      (node (ref "LED106") (pin "A") (pinfunction "A_A") (pintype "passive"))
      (node (ref "R142") (pin "1") (pinfunction "1_1") (pintype "passive"))
    )
    (net (code "154") (name "Net-(Q2-B)") (class "Default")
      (node (ref "Q2") (pin "1") (pinfunction "B_1") (pintype "passive"))
      (node (ref "R8") (pin "1") (pinfunction "1_1") (pintype "passive"))
    )
    (net (code "155") (name "Net-(Q2-C)") (class "Default")
      (node (ref "Q2") (pin "2") (pinfunction "C_2") (pintype "passive"))
      (node (ref "R129") (pin "2") (pinfunction "2_2") (pintype "passive"))
    )
    (net (code "156") (name "Net-(Q4-B)") (class "Default")
      (node (ref "Q4") (pin "1") (pinfunction "B_1") (pintype "passive"))
      (node (ref "R38") (pin "2") (pinfunction "2_2") (pintype "passive"))
    )
    (net (code "157") (name "Net-(Q5-B)") (class "Default")
      (node (ref "Q5") (pin "1") (pinfunction "B_1") (pintype "passive"))
      (node (ref "Q5") (pin "2") (pinfunction "C_2") (pintype "passive"))
      (node (ref "Q6") (pin "1") (pinfunction "B_1") (pintype "passive"))
      (node (ref "R33") (pin "1") (pinfunction "1_1") (pintype "passive"))
      (node (ref "R34") (pin "1") (pinfunction "1_1") (pintype "passive"))
      (node (ref "R58") (pin "1") (pinfunction "1_1") (pintype "passive"))
      (node (ref "X3") (pin "2") (pinfunction "S_2") (pintype "passive"))
    )
    (net (code "158") (name "Net-(Q5-E)") (class "Default")
      (node (ref "Q5") (pin "3") (pinfunction "E_3") (pintype "passive"))
      (node (ref "R39") (pin "2") (pinfunction "2_2") (pintype "passive"))
    )
    (net (code "159") (name "Net-(Q6-E)") (class "Default")
      (node (ref "Q6") (pin "3") (pinfunction "E_3") (pintype "passive"))
      (node (ref "R40") (pin "2") (pinfunction "2_2") (pintype "passive"))
    )
    (net (code "160") (name "Net-(Q7-B)") (class "Default")
      (node (ref "Q7") (pin "1") (pinfunction "B_1") (pintype "passive"))
      (node (ref "R31") (pin "1") (pinfunction "1_1") (pintype "passive"))
    )
    (net (code "161") (name "Net-(Q8-B)") (class "Default")
      (node (ref "Q8") (pin "1") (pinfunction "B_1") (pintype "passive"))
      (node (ref "R42") (pin "2") (pinfunction "2_2") (pintype "passive"))
      (node (ref "R63") (pin "1") (pinfunction "1_1") (pintype "passive"))
    )
    (net (code "162") (name "Net-(Q8-E)") (class "Default")
      (node (ref "Q8") (pin "3") (pinfunction "E_3") (pintype "passive"))
      (node (ref "R62") (pin "1") (pinfunction "1_1") (pintype "passive"))
    )
    (net (code "163") (name "Net-(Q9-D)") (class "Default")
      (node (ref "Q9") (pin "3") (pinfunction "D_3") (pintype "passive"))
      (node (ref "R43") (pin "2") (pinfunction "2_2") (pintype "passive"))
    )
    (net (code "164") (name "Net-(Q10-S)") (class "Default")
      (node (ref "Q10") (pin "2") (pinfunction "S_2") (pintype "passive"))
      (node (ref "R65") (pin "2") (pinfunction "2_2") (pintype "passive"))
    )
    (net (code "165") (name "Net-(Q12-B)") (class "Default")
      (node (ref "Q12") (pin "1") (pinfunction "B_1") (pintype "passive"))
      (node (ref "R67") (pin "1") (pinfunction "1_1") (pintype "passive"))
    )
    (net (code "166") (name "Net-(Q12-C)") (class "Default")
      (node (ref "Q12") (pin "2") (pinfunction "C_2") (pintype "passive"))
      (node (ref "R17") (pin "2") (pinfunction "2_2") (pintype "passive"))
    )
    (net (code "167") (name "Net-(Q101-B)") (class "Default")
      (node (ref "Q101") (pin "1") (pinfunction "B_1") (pintype "passive"))
      (node (ref "Q102") (pin "1") (pinfunction "B_1") (pintype "passive"))
      (node (ref "Q102") (pin "2") (pinfunction "C_2") (pintype "passive"))
      (node (ref "R101") (pin "1") (pinfunction "1_1") (pintype "passive"))
      (node (ref "R103") (pin "1") (pinfunction "1_1") (pintype "passive"))
      (node (ref "R104") (pin "1") (pinfunction "1_1") (pintype "passive"))
      (node (ref "X102") (pin "2") (pinfunction "S_2") (pintype "passive"))
    )
    (net (code "168") (name "Net-(Q101-E)") (class "Default")
      (node (ref "Q101") (pin "3") (pinfunction "E_3") (pintype "passive"))
      (node (ref "R102") (pin "2") (pinfunction "2_2") (pintype "passive"))
    )
    (net (code "169") (name "Net-(Q102-E)") (class "Default")
      (node (ref "Q102") (pin "3") (pinfunction "E_3") (pintype "passive"))
      (node (ref "R106") (pin "2") (pinfunction "2_2") (pintype "passive"))
    )
    (net (code "170") (name "Net-(Q103-B)") (class "Default")
      (node (ref "Q103") (pin "1") (pinfunction "B_1") (pintype "passive"))
      (node (ref "R116") (pin "2") (pinfunction "2_2") (pintype "passive"))
      (node (ref "R6") (pin "1") (pinfunction "1_1") (pintype "passive"))
    )
    (net (code "171") (name "Net-(Q103-E)") (class "Default")
      (node (ref "Q103") (pin "3") (pinfunction "E_3") (pintype "passive"))
      (node (ref "R5") (pin "1") (pinfunction "1_1") (pintype "passive"))
    )
    (net (code "172") (name "Net-(Q104-B)") (class "Default")
      (node (ref "Q104") (pin "1") (pinfunction "B_1") (pintype "passive"))
      (node (ref "R128") (pin "2") (pinfunction "2_2") (pintype "passive"))
    )
    (net (code "173") (name "Net-(Q105-B)") (class "Default")
      (node (ref "Q105") (pin "1") (pinfunction "B_1") (pintype "passive"))
      (node (ref "R126") (pin "1") (pinfunction "1_1") (pintype "passive"))
    )
    (net (code "174") (name "Net-(Q106-S)") (class "Default")
      (node (ref "Q106") (pin "2") (pinfunction "S_2") (pintype "passive"))
      (node (ref "R4") (pin "2") (pinfunction "2_2") (pintype "passive"))
    )
    (net (code "175") (name "Net-(Q107-D)") (class "Default")
      (node (ref "Q107") (pin "3") (pinfunction "D_3") (pintype "passive"))
      (node (ref "R138") (pin "2") (pinfunction "2_2") (pintype "passive"))
    )
    (net (code "176") (name "Net-(R15-Pad2)") (class "Default")
      (node (ref "R15") (pin "2") (pinfunction "2_2") (pintype "passive"))
      (node (ref "R17") (pin "1") (pinfunction "1_1") (pintype "passive"))
    )
    (net (code "177") (name "Net-(R35-Pad1)") (class "Default")
      (node (ref "R35") (pin "1") (pinfunction "1_1") (pintype "passive"))
      (node (ref "X1") (pin "21") (pinfunction "21_21") (pintype "passive"))
    )
    (net (code "178") (name "Net-(R47-Pad2)") (class "Default")
      (node (ref "R47") (pin "2") (pinfunction "2_2") (pintype "passive"))
      (node (ref "X1") (pin "16") (pinfunction "16_16") (pintype "passive"))
    )
    (net (code "179") (name "Net-(R115-Pad1)") (class "Default")
      (node (ref "R115") (pin "1") (pinfunction "1_1") (pintype "passive"))
      (node (ref "X101") (pin "21") (pinfunction "21_21") (pintype "passive"))
    )
    (net (code "180") (name "Net-(R127-Pad2)") (class "Default")
      (node (ref "R127") (pin "2") (pinfunction "2_2") (pintype "passive"))
      (node (ref "R129") (pin "1") (pinfunction "1_1") (pintype "passive"))
    )
    (net (code "181") (name "Net-(R140-Pad2)") (class "Default")
      (node (ref "R140") (pin "2") (pinfunction "2_2") (pintype "passive"))
      (node (ref "X101") (pin "16") (pinfunction "16_16") (pintype "passive"))
    )
    (net (code "182") (name "V+") (class "Default")
      (node (ref "D1") (pin "1") (pinfunction "+_1") (pintype "passive"))
      (node (ref "D15") (pin "1") (pinfunction "+_1") (pintype "passive"))
      (node (ref "Q104") (pin "3") (pinfunction "E_3") (pintype "passive"))
      (node (ref "Q105") (pin "3") (pinfunction "E_3") (pintype "passive"))
      (node (ref "Q12") (pin "3") (pinfunction "E_3") (pintype "passive"))
      (node (ref "Q2") (pin "3") (pinfunction "E_3") (pintype "passive"))
      (node (ref "Q4") (pin "3") (pinfunction "E_3") (pintype "passive"))
      (node (ref "Q7") (pin "3") (pinfunction "E_3") (pintype "passive"))
      (node (ref "X1") (pin "6") (pinfunction "6_6") (pintype "passive"))
      (node (ref "X101") (pin "6") (pinfunction "6_6") (pintype "passive"))
    )
    (net (code "183") (name "VCC") (class "Default")
      (node (ref "6V") (pin "TP") (pinfunction "PP_TP") (pintype "input"))
      (node (ref "6V1") (pin "TP") (pinfunction "PP_TP") (pintype "input"))
      (node (ref "C104") (pin "1") (pinfunction "1_1") (pintype "passive"))
      (node (ref "C5") (pin "1") (pinfunction "1_1") (pintype "passive"))
      (node (ref "IC101") (pin "8") (pinfunction "V+_8") (pintype "power_in"))
      (node (ref "IC102") (pin "1") (pinfunction "OUT_1") (pintype "passive"))
      (node (ref "IC103") (pin "OUT") (pinfunction "OUT_OUT") (pintype "passive"))
      (node (ref "IC108") (pin "3") (pinfunction "V+_3") (pintype "power_in"))
      (node (ref "IC11") (pin "8") (pinfunction "V+_8") (pintype "power_in"))
      (node (ref "IC3") (pin "OUT") (pinfunction "OUT_OUT") (pintype "passive"))
      (node (ref "IC6") (pin "3") (pinfunction "V+_3") (pintype "power_in"))
      (node (ref "IC7") (pin "1") (pinfunction "OUT_1") (pintype "passive"))
      (node (ref "R113") (pin "2") (pinfunction "2_2") (pintype "passive"))
      (node (ref "R121") (pin "2") (pinfunction "2_2") (pintype "passive"))
      (node (ref "R124") (pin "1") (pinfunction "1_1") (pintype "passive"))
      (node (ref "R131") (pin "2") (pinfunction "2_2") (pintype "passive"))
      (node (ref "R142") (pin "2") (pinfunction "2_2") (pintype "passive"))
      (node (ref "R24") (pin "2") (pinfunction "2_2") (pintype "passive"))
      (node (ref "R27") (pin "2") (pinfunction "2_2") (pintype "passive"))
      (node (ref "R30") (pin "1") (pinfunction "1_1") (pintype "passive"))
      (node (ref "R37") (pin "2") (pinfunction "2_2") (pintype "passive"))
      (node (ref "R56") (pin "2") (pinfunction "2_2") (pintype "passive"))
    )
    (net (code "184") (name "unconnected-(IC1-ON-Pad5)") (class "Default")
      (node (ref "IC1") (pin "5") (pinfunction "ON_5") (pintype "passive"))
    )
    (net (code "185") (name "unconnected-(IC1-ON{slash}STR-Pad6)") (class "Default")
      (node (ref "IC1") (pin "6") (pinfunction "ON/STR_6") (pintype "passive"))
    )
    (net (code "186") (name "unconnected-(IC2A-Q6-Pad7)") (class "Default")
      (node (ref "IC2") (pin "7") (pinfunction "Q6_7") (pintype "output"))
    )
    (net (code "187") (name "unconnected-(IC2A-Q7-Pad4)") (class "Default")
      (node (ref "IC2") (pin "4") (pinfunction "Q7_4") (pintype "output"))
    )
    (net (code "188") (name "unconnected-(IC2A-Q8-Pad9)") (class "Default")
      (node (ref "IC2") (pin "9") (pinfunction "Q8_9") (pintype "output"))
    )
    (net (code "189") (name "unconnected-(IC2A-Q9-Pad5)") (class "Default")
      (node (ref "IC2") (pin "5") (pinfunction "Q9_5") (pintype "output"))
    )
    (net (code "190") (name "unconnected-(IC8-DIS-Pad7)") (class "Default")
      (node (ref "IC8") (pin "7") (pinfunction "DIS_7") (pintype "input"))
    )
    (net (code "191") (name "unconnected-(IC9A-Q-Pad6)") (class "Default")
      (node (ref "IC9") (pin "6") (pinfunction "Q_6") (pintype "output"))
    )
    (net (code "192") (name "unconnected-(IC9A-T2-Pad2)") (class "Default")
      (node (ref "IC9") (pin "2") (pinfunction "T2_2") (pintype "input"))
    )
    (net (code "193") (name "unconnected-(IC9A-~{Q}-Pad7)") (class "Default")
      (node (ref "IC9") (pin "7") (pinfunction "~{Q}_7") (pintype "output"))
    )
    (net (code "194") (name "unconnected-(IC12-ON-Pad5)") (class "Default")
      (node (ref "IC12") (pin "5") (pinfunction "ON_5") (pintype "passive"))
    )
    (net (code "195") (name "unconnected-(IC12-ON{slash}STR-Pad6)") (class "Default")
      (node (ref "IC12") (pin "6") (pinfunction "ON/STR_6") (pintype "passive"))
    )
    (net (code "196") (name "unconnected-(IC105A-Q6-Pad7)") (class "Default")
      (node (ref "IC105") (pin "7") (pinfunction "Q6_7") (pintype "output"))
    )
    (net (code "197") (name "unconnected-(IC105A-Q7-Pad4)") (class "Default")
      (node (ref "IC105") (pin "4") (pinfunction "Q7_4") (pintype "output"))
    )
    (net (code "198") (name "unconnected-(IC105A-Q8-Pad9)") (class "Default")
      (node (ref "IC105") (pin "9") (pinfunction "Q8_9") (pintype "output"))
    )
    (net (code "199") (name "unconnected-(IC105A-Q9-Pad5)") (class "Default")
      (node (ref "IC105") (pin "5") (pinfunction "Q9_5") (pintype "output"))
    )
    (net (code "200") (name "unconnected-(IC110-DIS-Pad7)") (class "Default")
      (node (ref "IC110") (pin "7") (pinfunction "DIS_7") (pintype "input"))
    )
    (net (code "201") (name "unconnected-(IC111A-Q-Pad6)") (class "Default")
      (node (ref "IC111") (pin "6") (pinfunction "Q_6") (pintype "output"))
    )
    (net (code "202") (name "unconnected-(IC111A-T2-Pad2)") (class "Default")
      (node (ref "IC111") (pin "2") (pinfunction "T2_2") (pintype "input"))
    )
    (net (code "203") (name "unconnected-(IC111A-~{Q}-Pad7)") (class "Default")
      (node (ref "IC111") (pin "7") (pinfunction "~{Q}_7") (pintype "output"))
    )
    (net (code "204") (name "unconnected-(Q3-G-Pad1)") (class "Default")
      (node (ref "Q3") (pin "1") (pinfunction "G_1") (pintype "passive"))
    )
    (net (code "205") (name "unconnected-(Q13-G-Pad1)") (class "Default")
      (node (ref "Q13") (pin "1") (pinfunction "G_1") (pintype "passive"))
    )
    (net (code "206") (name "unconnected-(X1-Pad20)") (class "Default")
      (node (ref "X1") (pin "20") (pinfunction "20_20") (pintype "passive"))
    )
    (net (code "207") (name "unconnected-(X1-Pad24)") (class "Default")
      (node (ref "X1") (pin "24") (pinfunction "24_24") (pintype "passive"))
    )
    (net (code "208") (name "unconnected-(X101-Pad20)") (class "Default")
      (node (ref "X101") (pin "20") (pinfunction "20_20") (pintype "passive"))
    )
    (net (code "209") (name "unconnected-(X101-Pad24)") (class "Default")
      (node (ref "X101") (pin "24") (pinfunction "24_24") (pintype "passive"))
    )
  )
)
